# IceCore.net
KiCad netlist of a schematic drawn in EAGLE
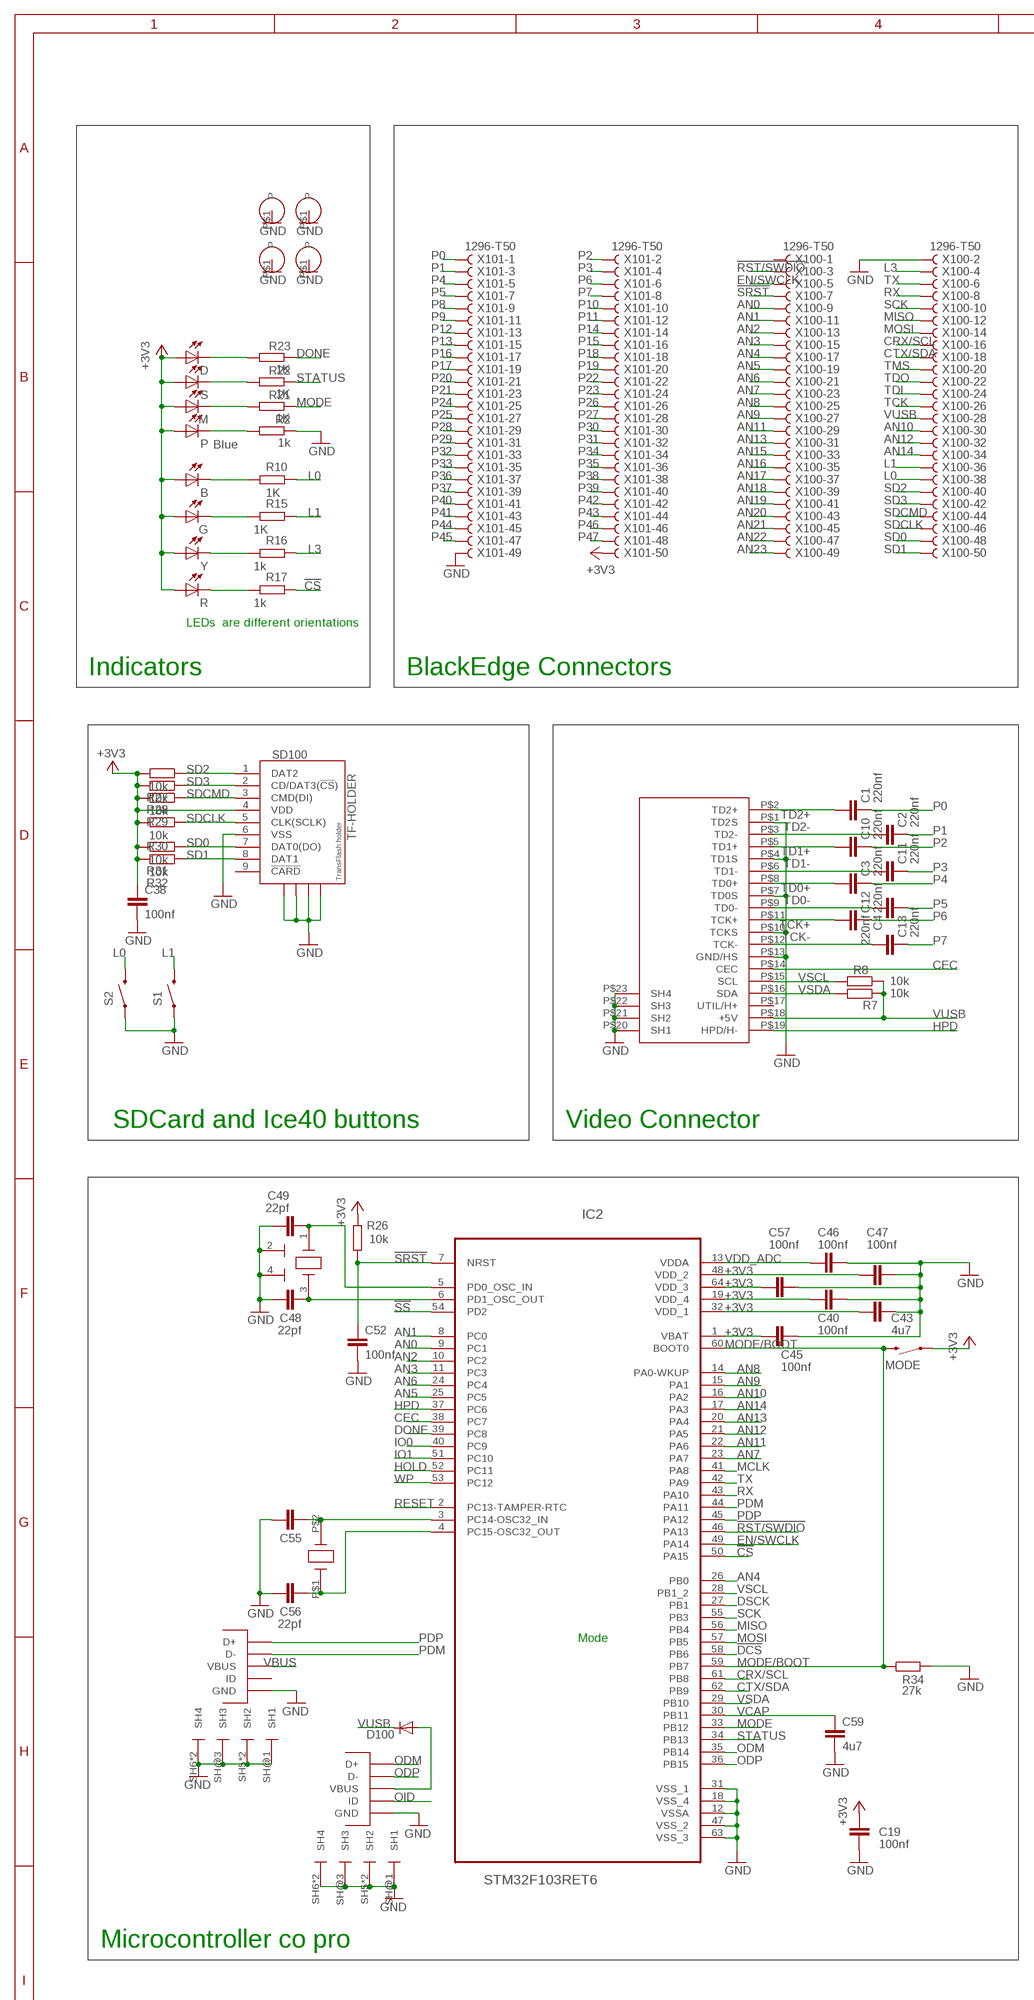
[diagram p0: schematic, sheet 1, part 1 of 2]
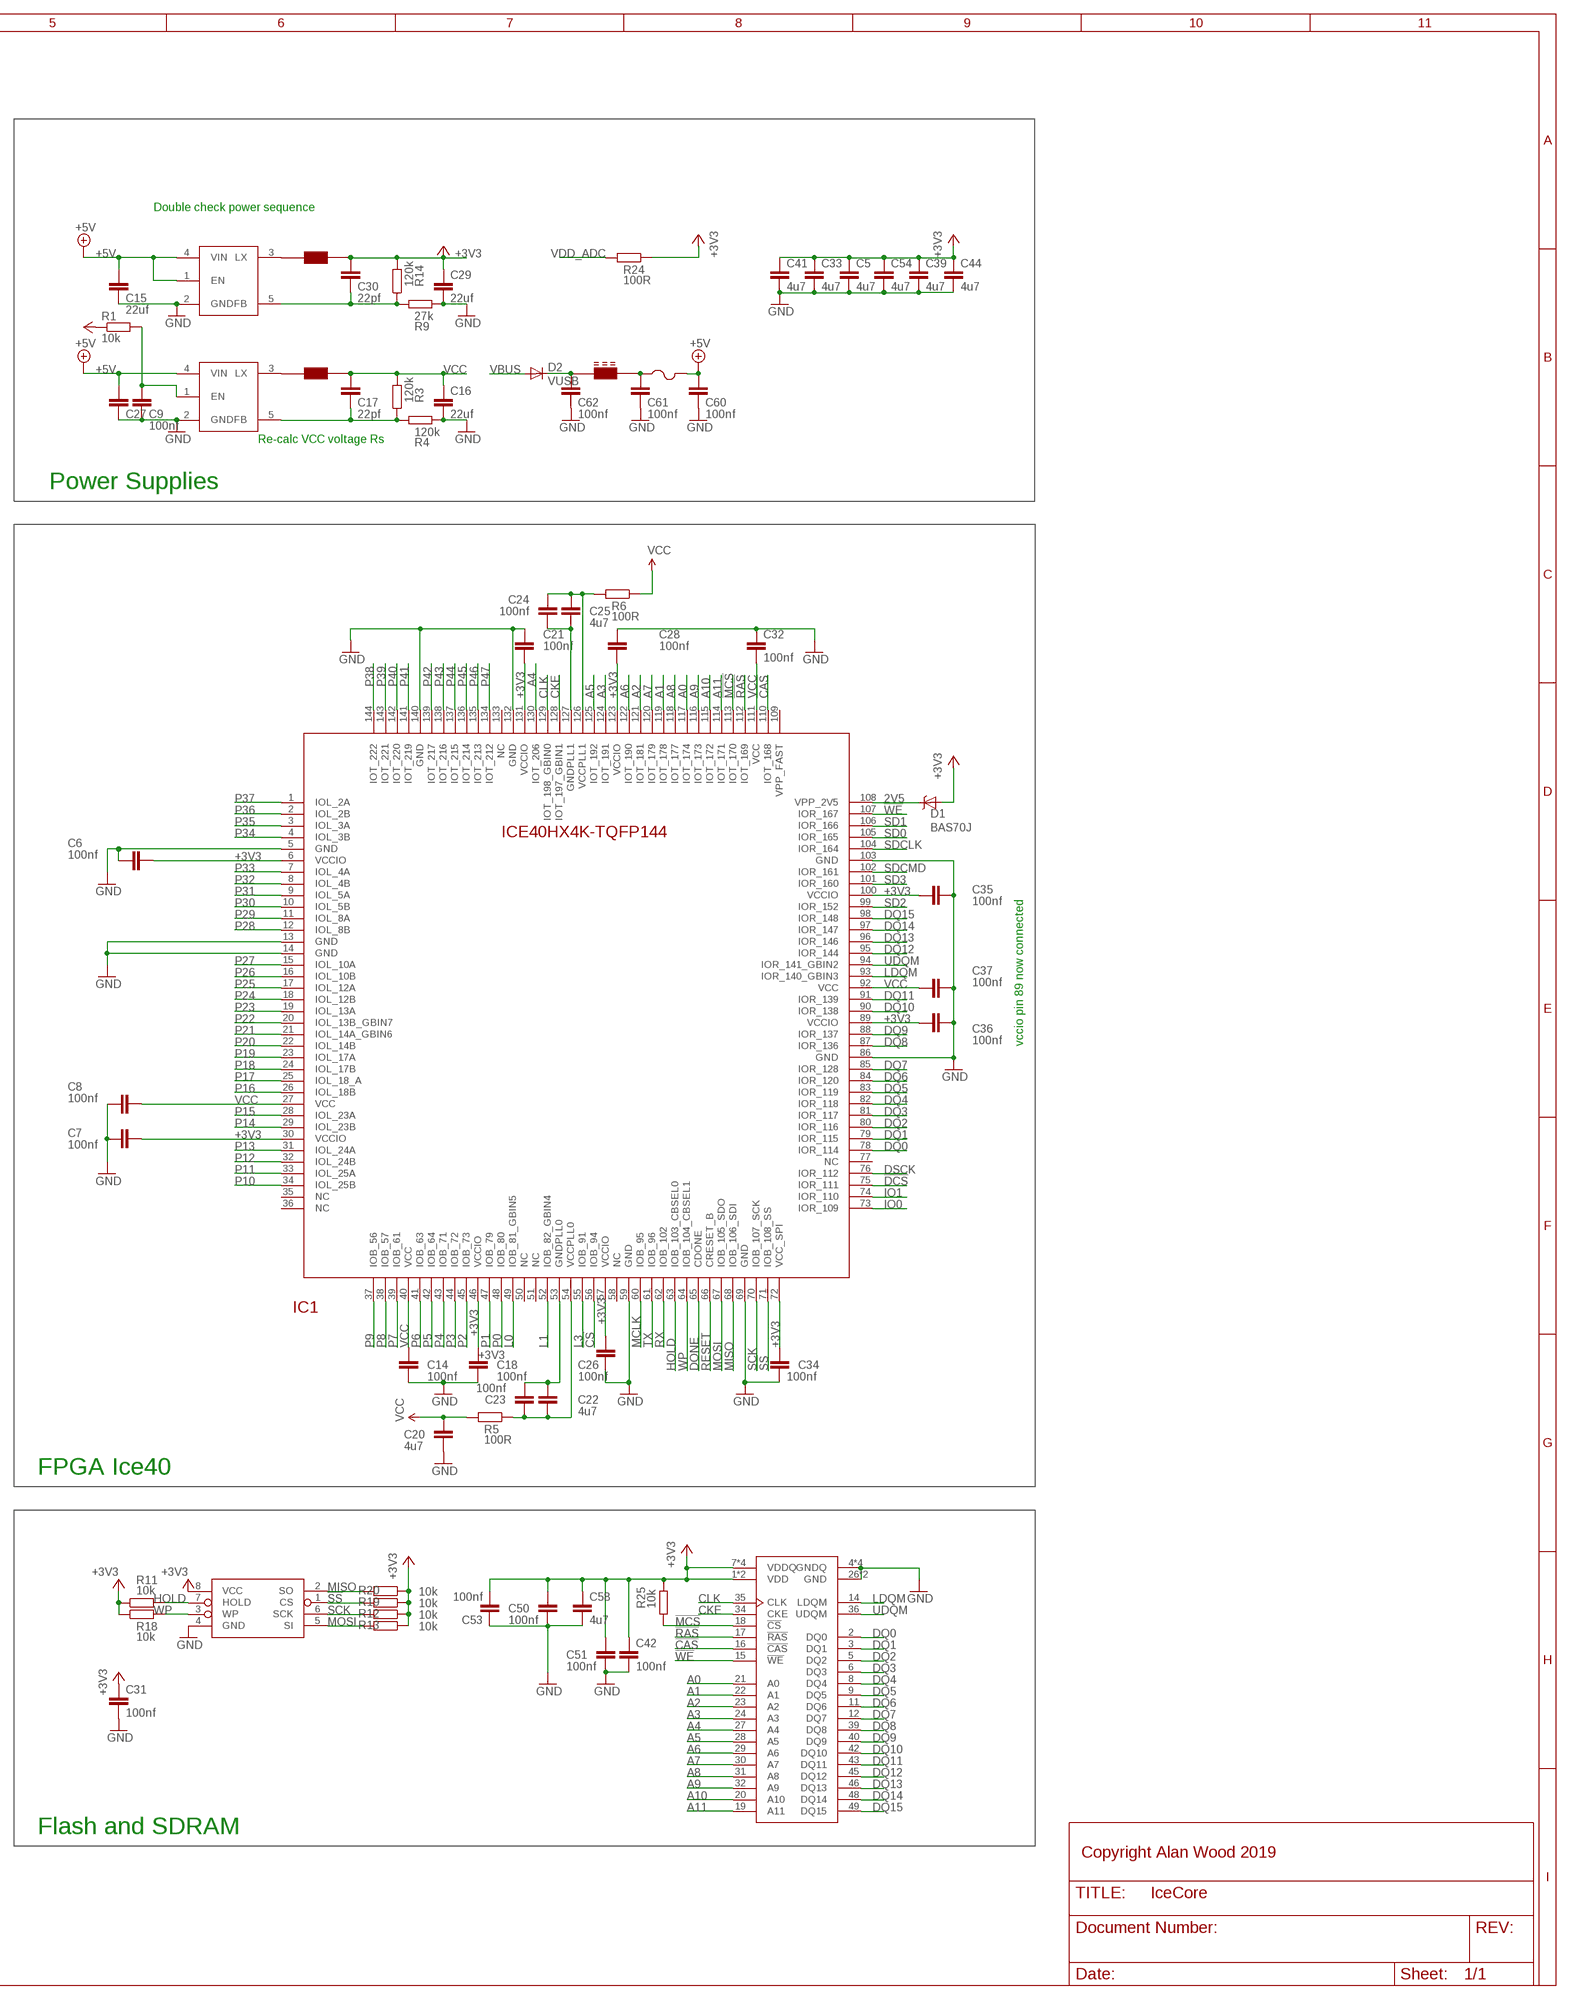
[diagram p1: schematic, sheet 1, part 2 of 2]

(export (version "E")
  (design (tool "Eeschema 10.0.6"))
  (components
    (comp (ref "B")
      (value "LEDCHIPLED_0603")
      (footprint "eagle-import:CHIPLED_0603")
      (libsource (lib "eagle-import") (part "LEDCHIPLED_0603"))
    )
    (comp (ref "C1")
      (value "220nf")
      (footprint "eagle-import:C0402")
      (libsource (lib "eagle-import") (part "C-EUC0402"))
    )
    (comp (ref "C2")
      (value "220nf")
      (footprint "eagle-import:C0402")
      (libsource (lib "eagle-import") (part "C-EUC0402"))
    )
    (comp (ref "C3")
      (value "220nf")
      (footprint "eagle-import:C0402")
      (libsource (lib "eagle-import") (part "C-EUC0402"))
    )
    (comp (ref "C4")
      (value "220nf")
      (footprint "eagle-import:C0402")
      (libsource (lib "eagle-import") (part "C-EUC0402"))
    )
    (comp (ref "C5")
      (value "4u7")
      (footprint "eagle-import:C0402")
      (libsource (lib "eagle-import") (part "C-EUC0402"))
    )
    (comp (ref "C6")
      (value "100nf")
      (footprint "eagle-import:C0402")
      (libsource (lib "eagle-import") (part "C-EUC0402"))
    )
    (comp (ref "C7")
      (value "100nf")
      (footprint "eagle-import:C0402")
      (libsource (lib "eagle-import") (part "C-EUC0402"))
    )
    (comp (ref "C8")
      (value "100nf")
      (footprint "eagle-import:C0402")
      (libsource (lib "eagle-import") (part "C-EUC0402"))
    )
    (comp (ref "C9")
      (value "100nf")
      (footprint "eagle-import:C0402")
      (libsource (lib "eagle-import") (part "C-EUC0402"))
    )
    (comp (ref "C10")
      (value "220nf")
      (footprint "eagle-import:C0402")
      (libsource (lib "eagle-import") (part "C-EUC0402"))
    )
    (comp (ref "C11")
      (value "220nf")
      (footprint "eagle-import:C0402")
      (libsource (lib "eagle-import") (part "C-EUC0402"))
    )
    (comp (ref "C12")
      (value "220nf")
      (footprint "eagle-import:C0402")
      (libsource (lib "eagle-import") (part "C-EUC0402"))
    )
    (comp (ref "C13")
      (value "220nf")
      (footprint "eagle-import:C0402")
      (libsource (lib "eagle-import") (part "C-EUC0402"))
    )
    (comp (ref "C14")
      (value "100nf")
      (footprint "eagle-import:C0402")
      (libsource (lib "eagle-import") (part "C-EUC0402"))
    )
    (comp (ref "C15")
      (value "22uf")
      (footprint "eagle-import:C0603")
      (libsource (lib "eagle-import") (part "C-EUC0603"))
    )
    (comp (ref "C16")
      (value "22uf")
      (footprint "eagle-import:C0603")
      (libsource (lib "eagle-import") (part "C-EUC0603"))
    )
    (comp (ref "C17")
      (value "22pf")
      (footprint "eagle-import:C0402")
      (libsource (lib "eagle-import") (part "C-EUC0402"))
    )
    (comp (ref "C18")
      (value "100nf")
      (footprint "eagle-import:C0402")
      (libsource (lib "eagle-import") (part "C-EUC0402"))
    )
    (comp (ref "C19")
      (value "100nf")
      (footprint "eagle-import:C0402")
      (libsource (lib "eagle-import") (part "C-EUC0402"))
    )
    (comp (ref "C20")
      (value "4u7")
      (footprint "eagle-import:C0402")
      (libsource (lib "eagle-import") (part "C-EUC0402"))
    )
    (comp (ref "C21")
      (value "100nf")
      (footprint "eagle-import:C0402")
      (libsource (lib "eagle-import") (part "C-EUC0402"))
    )
    (comp (ref "C22")
      (value "4u7")
      (footprint "eagle-import:C0402")
      (libsource (lib "eagle-import") (part "C-EUC0402"))
    )
    (comp (ref "C23")
      (value "100nf")
      (footprint "eagle-import:C0402")
      (libsource (lib "eagle-import") (part "C-EUC0402"))
    )
    (comp (ref "C24")
      (value "100nf")
      (footprint "eagle-import:C0402")
      (libsource (lib "eagle-import") (part "C-EUC0402"))
    )
    (comp (ref "C25")
      (value "4u7")
      (footprint "eagle-import:C0402")
      (libsource (lib "eagle-import") (part "C-EUC0402"))
    )
    (comp (ref "C26")
      (value "100nf")
      (footprint "eagle-import:C0402")
      (libsource (lib "eagle-import") (part "C-EUC0402"))
    )
    (comp (ref "C27")
      (value "22uf")
      (footprint "eagle-import:C0603")
      (libsource (lib "eagle-import") (part "C-EUC0603"))
    )
    (comp (ref "C28")
      (value "100nf")
      (footprint "eagle-import:C0402")
      (libsource (lib "eagle-import") (part "C-EUC0402"))
    )
    (comp (ref "C29")
      (value "22uf")
      (footprint "eagle-import:C0603")
      (libsource (lib "eagle-import") (part "C-EUC0603"))
    )
    (comp (ref "C30")
      (value "22pf")
      (footprint "eagle-import:C0402")
      (libsource (lib "eagle-import") (part "C-EUC0402"))
    )
    (comp (ref "C31")
      (value "100nf")
      (footprint "eagle-import:C0402")
      (libsource (lib "eagle-import") (part "C-EUC0402"))
    )
    (comp (ref "C32")
      (value "100nf")
      (footprint "eagle-import:C0402")
      (libsource (lib "eagle-import") (part "C-EUC0402"))
    )
    (comp (ref "C33")
      (value "4u7")
      (footprint "eagle-import:C0402")
      (libsource (lib "eagle-import") (part "C-EUC0402"))
    )
    (comp (ref "C34")
      (value "100nf")
      (footprint "eagle-import:C0402")
      (libsource (lib "eagle-import") (part "C-EUC0402"))
    )
    (comp (ref "C35")
      (value "100nf")
      (footprint "eagle-import:C0402")
      (libsource (lib "eagle-import") (part "C-EUC0402"))
    )
    (comp (ref "C36")
      (value "100nf")
      (footprint "eagle-import:C0402")
      (libsource (lib "eagle-import") (part "C-EUC0402"))
    )
    (comp (ref "C37")
      (value "100nf")
      (footprint "eagle-import:C0402")
      (libsource (lib "eagle-import") (part "C-EUC0402"))
    )
    (comp (ref "C38")
      (value "100nf")
      (footprint "eagle-import:C0402")
      (libsource (lib "eagle-import") (part "C-EUC0402"))
    )
    (comp (ref "C39")
      (value "4u7")
      (footprint "eagle-import:C0402")
      (libsource (lib "eagle-import") (part "C-EUC0402"))
    )
    (comp (ref "C40")
      (value "100nf")
      (footprint "eagle-import:C0402")
      (libsource (lib "eagle-import") (part "C-EUC0402"))
    )
    (comp (ref "C41")
      (value "4u7")
      (footprint "eagle-import:C0402")
      (libsource (lib "eagle-import") (part "C-EUC0402"))
    )
    (comp (ref "C42")
      (value "100nf")
      (footprint "eagle-import:C0402")
      (libsource (lib "eagle-import") (part "C-EUC0402"))
    )
    (comp (ref "C43")
      (value "4u7")
      (footprint "eagle-import:C0402")
      (libsource (lib "eagle-import") (part "C-EUC0402"))
    )
    (comp (ref "C44")
      (value "4u7")
      (footprint "eagle-import:C0402")
      (libsource (lib "eagle-import") (part "C-EUC0402"))
    )
    (comp (ref "C45")
      (value "100nf")
      (footprint "eagle-import:C0402")
      (libsource (lib "eagle-import") (part "C-EUC0402"))
    )
    (comp (ref "C46")
      (value "100nf")
      (footprint "eagle-import:C0402")
      (libsource (lib "eagle-import") (part "C-EUC0402"))
    )
    (comp (ref "C47")
      (value "100nf")
      (footprint "eagle-import:C0402")
      (libsource (lib "eagle-import") (part "C-EUC0402"))
    )
    (comp (ref "C48")
      (value "22pf")
      (footprint "eagle-import:C0402")
      (libsource (lib "eagle-import") (part "C-EUC0402"))
    )
    (comp (ref "C49")
      (value "22pf")
      (footprint "eagle-import:C0402")
      (libsource (lib "eagle-import") (part "C-EUC0402"))
    )
    (comp (ref "C50")
      (value "100nf")
      (footprint "eagle-import:C0402")
      (libsource (lib "eagle-import") (part "C-EUC0402"))
    )
    (comp (ref "C51")
      (value "100nf")
      (footprint "eagle-import:C0402")
      (libsource (lib "eagle-import") (part "C-EUC0402"))
    )
    (comp (ref "C52")
      (value "100nf")
      (footprint "eagle-import:C0402")
      (libsource (lib "eagle-import") (part "C-EUC0402"))
    )
    (comp (ref "C53")
      (value "100nf")
      (footprint "eagle-import:C0402")
      (libsource (lib "eagle-import") (part "C-EUC0402"))
    )
    (comp (ref "C54")
      (value "4u7")
      (footprint "eagle-import:C0402")
      (libsource (lib "eagle-import") (part "C-EUC0402"))
    )
    (comp (ref "C55")
      (value "22pf")
      (footprint "eagle-import:C0402")
      (libsource (lib "eagle-import") (part "C-EUC0402"))
    )
    (comp (ref "C56")
      (value "22pf")
      (footprint "eagle-import:C0402")
      (libsource (lib "eagle-import") (part "C-EUC0402"))
    )
    (comp (ref "C57")
      (value "100nf")
      (footprint "eagle-import:C0402")
      (libsource (lib "eagle-import") (part "C-EUC0402"))
    )
    (comp (ref "C58")
      (value "4u7")
      (footprint "eagle-import:C0402")
      (libsource (lib "eagle-import") (part "C-EUC0402"))
    )
    (comp (ref "C59")
      (value "4u7")
      (footprint "eagle-import:C0402")
      (libsource (lib "eagle-import") (part "C-EUC0402"))
    )
    (comp (ref "C60")
      (value "100nf")
      (footprint "eagle-import:C0402")
      (libsource (lib "eagle-import") (part "C-EUC0402"))
    )
    (comp (ref "C61")
      (value "100nf")
      (footprint "eagle-import:C0402")
      (libsource (lib "eagle-import") (part "C-EUC0402"))
    )
    (comp (ref "C62")
      (value "100nf")
      (footprint "eagle-import:C0402")
      (libsource (lib "eagle-import") (part "C-EUC0402"))
    )
    (comp (ref "COM")
      (value "FCI-MICROUSB-B-PEG")
      (footprint "eagle-import:MICROUSB-B-PEG")
      (libsource (lib "eagle-import") (part "FCI-MICROUSB-B-PEG"))
    )
    (comp (ref "D")
      (value "LEDCHIPLED_0603")
      (footprint "eagle-import:CHIPLED_0603")
      (libsource (lib "eagle-import") (part "LEDCHIPLED_0603"))
    )
    (comp (ref "D1")
      (value "BAS70J")
      (footprint "eagle-import:SOD-323")
      (libsource (lib "eagle-import") (part "BAS70J"))
    )
    (comp (ref "D2")
      (value "DIODE-SOD123")
      (footprint "eagle-import:SOD123")
      (libsource (lib "eagle-import") (part "DIODE-SOD123"))
    )
    (comp (ref "D100")
      (value "DIODE-SOD123")
      (footprint "eagle-import:SOD123")
      (libsource (lib "eagle-import") (part "DIODE-SOD123"))
    )
    (comp (ref "F1")
      (value "PTCFUSE-1206")
      (footprint "eagle-import:R1206")
      (libsource (lib "eagle-import") (part "PTCFUSE-1206"))
    )
    (comp (ref "FB1")
      (value "FERRITE_BEAD")
      (footprint "eagle-import:0603")
      (libsource (lib "eagle-import") (part "FERRITE_BEAD"))
    )
    (comp (ref "G")
      (value "LEDCHIPLED_0603")
      (footprint "eagle-import:CHIPLED_0603")
      (libsource (lib "eagle-import") (part "LEDCHIPLED_0603"))
    )
    (comp (ref "IC1")
      (value "ICE40HX4K_TQFP144")
      (footprint "eagle-import:TQFP144")
      (libsource (lib "eagle-import") (part "ICE40HX4K_TQFP144"))
    )
    (comp (ref "IC2")
      (value "STM32F103RET6")
      (footprint "eagle-import:QFP50P1200X1200X160-64N")
      (libsource (lib "eagle-import") (part "STM32F103RET6"))
    )
    (comp (ref "IC3")
      (value "SDRAM")
      (footprint "eagle-import:TSOP-2-50")
      (libsource (lib "eagle-import") (part "SDRAM"))
    )
    (comp (ref "M")
      (value "LEDCHIPLED_0603")
      (footprint "eagle-import:CHIPLED_0603")
      (libsource (lib "eagle-import") (part "LEDCHIPLED_0603"))
    )
    (comp (ref "MODE")
      (value "SWITCH-MOMENTARY-2SMD-1101NE")
      (footprint "eagle-import:TACTILE-SWITCH-1101NE")
      (libsource (lib "eagle-import") (part "SWITCH-MOMENTARY-2SMD-1101NE"))
    )
    (comp (ref "P")
      (value "Blue")
      (footprint "eagle-import:CHIPLED_0603")
      (libsource (lib "eagle-import") (part "LEDCHIPLED_0603"))
    )
    (comp (ref "R")
      (value "LEDCHIPLED_0603")
      (footprint "eagle-import:CHIPLED_0603")
      (libsource (lib "eagle-import") (part "LEDCHIPLED_0603"))
    )
    (comp (ref "R1")
      (value "10k")
      (footprint "eagle-import:R0402")
      (libsource (lib "eagle-import") (part "resistor_R-EU_R0402"))
    )
    (comp (ref "R2")
      (value "1k")
      (footprint "eagle-import:R0402")
      (libsource (lib "eagle-import") (part "resistor_R-EU_R0402"))
    )
    (comp (ref "R3")
      (value "120k")
      (footprint "eagle-import:R0402")
      (libsource (lib "eagle-import") (part "resistor_R-EU_R0402"))
    )
    (comp (ref "R4")
      (value "120k")
      (footprint "eagle-import:R0402")
      (libsource (lib "eagle-import") (part "resistor_R-EU_R0402"))
    )
    (comp (ref "R5")
      (value "100R")
      (footprint "eagle-import:R0402")
      (libsource (lib "eagle-import") (part "resistor_R-EU_R0402"))
    )
    (comp (ref "R6")
      (value "100R")
      (footprint "eagle-import:R0402")
      (libsource (lib "eagle-import") (part "resistor_R-EU_R0402"))
    )
    (comp (ref "R7")
      (value "10k")
      (footprint "eagle-import:R0402")
      (libsource (lib "eagle-import") (part "resistor_R-EU_R0402"))
    )
    (comp (ref "R8")
      (value "10k")
      (footprint "eagle-import:R0402")
      (libsource (lib "eagle-import") (part "resistor_R-EU_R0402"))
    )
    (comp (ref "R9")
      (value "27k")
      (footprint "eagle-import:R0402")
      (libsource (lib "eagle-import") (part "resistor_R-EU_R0402"))
    )
    (comp (ref "R10")
      (value "1K")
      (footprint "eagle-import:R0402")
      (libsource (lib "eagle-import") (part "resistor_R-EU_R0402"))
    )
    (comp (ref "R11")
      (value "10k")
      (footprint "eagle-import:R0402")
      (libsource (lib "eagle-import") (part "resistor_R-EU_R0402"))
    )
    (comp (ref "R12")
      (value "10k")
      (footprint "eagle-import:R0402")
      (libsource (lib "eagle-import") (part "resistor_R-EU_R0402"))
    )
    (comp (ref "R13")
      (value "10k")
      (footprint "eagle-import:R0402")
      (libsource (lib "eagle-import") (part "resistor_R-EU_R0402"))
    )
    (comp (ref "R14")
      (value "120k")
      (footprint "eagle-import:R0402")
      (libsource (lib "eagle-import") (part "resistor_R-EU_R0402"))
    )
    (comp (ref "R15")
      (value "1K")
      (footprint "eagle-import:R0402")
      (libsource (lib "eagle-import") (part "resistor_R-EU_R0402"))
    )
    (comp (ref "R16")
      (value "1k")
      (footprint "eagle-import:R0402")
      (libsource (lib "eagle-import") (part "resistor_R-EU_R0402"))
    )
    (comp (ref "R17")
      (value "1k")
      (footprint "eagle-import:R0402")
      (libsource (lib "eagle-import") (part "resistor_R-EU_R0402"))
    )
    (comp (ref "R18")
      (value "10k")
      (footprint "eagle-import:R0402")
      (libsource (lib "eagle-import") (part "resistor_R-EU_R0402"))
    )
    (comp (ref "R19")
      (value "10k")
      (footprint "eagle-import:R0402")
      (libsource (lib "eagle-import") (part "resistor_R-EU_R0402"))
    )
    (comp (ref "R20")
      (value "10k")
      (footprint "eagle-import:R0402")
      (libsource (lib "eagle-import") (part "resistor_R-EU_R0402"))
    )
    (comp (ref "R21")
      (value "1K")
      (footprint "eagle-import:R0402")
      (libsource (lib "eagle-import") (part "resistor_R-EU_R0402"))
    )
    (comp (ref "R22")
      (value "1K")
      (footprint "eagle-import:R0402")
      (libsource (lib "eagle-import") (part "resistor_R-EU_R0402"))
    )
    (comp (ref "R23")
      (value "1K")
      (footprint "eagle-import:R0402")
      (libsource (lib "eagle-import") (part "resistor_R-EU_R0402"))
    )
    (comp (ref "R24")
      (value "100R")
      (footprint "eagle-import:R0402")
      (libsource (lib "eagle-import") (part "resistor_R-EU_R0402"))
    )
    (comp (ref "R25")
      (value "10k")
      (footprint "eagle-import:R0402")
      (libsource (lib "eagle-import") (part "resistor_R-EU_R0402"))
    )
    (comp (ref "R26")
      (value "10k")
      (footprint "eagle-import:R0402")
      (libsource (lib "eagle-import") (part "R-EU_R0402"))
    )
    (comp (ref "R27")
      (value "10k")
      (footprint "eagle-import:R0402")
      (libsource (lib "eagle-import") (part "resistor_R-EU_R0402"))
    )
    (comp (ref "R28")
      (value "10k")
      (footprint "eagle-import:R0402")
      (libsource (lib "eagle-import") (part "resistor_R-EU_R0402"))
    )
    (comp (ref "R29")
      (value "10k")
      (footprint "eagle-import:R0402")
      (libsource (lib "eagle-import") (part "resistor_R-EU_R0402"))
    )
    (comp (ref "R30")
      (value "10k")
      (footprint "eagle-import:R0402")
      (libsource (lib "eagle-import") (part "resistor_R-EU_R0402"))
    )
    (comp (ref "R31")
      (value "10k")
      (footprint "eagle-import:R0402")
      (libsource (lib "eagle-import") (part "resistor_R-EU_R0402"))
    )
    (comp (ref "R32")
      (value "10k")
      (footprint "eagle-import:R0402")
      (libsource (lib "eagle-import") (part "resistor_R-EU_R0402"))
    )
    (comp (ref "R34")
      (value "27k")
      (footprint "eagle-import:R0402")
      (libsource (lib "eagle-import") (part "resistor_R-EU_R0402"))
    )
    (comp (ref "S")
      (value "LEDCHIPLED_0603")
      (footprint "eagle-import:CHIPLED_0603")
      (libsource (lib "eagle-import") (part "LEDCHIPLED_0603"))
    )
    (comp (ref "S1")
      (value "SWITCH-MOMENTARY-2SMD-1101NE")
      (footprint "eagle-import:TACTILE-SWITCH-1101NE")
      (libsource (lib "eagle-import") (part "SWITCH-MOMENTARY-2SMD-1101NE"))
    )
    (comp (ref "S2")
      (value "SWITCH-MOMENTARY-2SMD-1101NE")
      (footprint "eagle-import:TACTILE-SWITCH-1101NE")
      (libsource (lib "eagle-import") (part "SWITCH-MOMENTARY-2SMD-1101NE"))
    )
    (comp (ref "SD100")
      (value "TF-HOLDER")
      (footprint "eagle-import:TF-PULL")
      (libsource (lib "eagle-import") (part "TF-HOLDER"))
    )
    (comp (ref "U$1")
      (value "HOLE-2.5MM")
      (footprint "eagle-import:2.5MM-HOLE")
      (libsource (lib "eagle-import") (part "HOLE-2.5MM"))
    )
    (comp (ref "U$2")
      (value "HOLE-2.5MM")
      (footprint "eagle-import:2.5MM-HOLE")
      (libsource (lib "eagle-import") (part "HOLE-2.5MM"))
    )
    (comp (ref "U$3")
      (value "AP3429/A")
      (footprint "eagle-import:TSOP-5_SOT23-5")
      (libsource (lib "eagle-import") (part "AP3429/A"))
    )
    (comp (ref "U$4")
      (value "NRS4018")
      (footprint "eagle-import:NRC4018")
      (libsource (lib "eagle-import") (part "NRS4018"))
    )
    (comp (ref "U$5")
      (value "HD10-001_HDMIMINI-HDMI")
      (footprint "eagle-import:MINI-HDMI")
      (libsource (lib "eagle-import") (part "HD10-001_HDMIMINI-HDMI"))
    )
    (comp (ref "U$6")
      (value "AP3429/A")
      (footprint "eagle-import:TSOP-5_SOT23-5")
      (libsource (lib "eagle-import") (part "AP3429/A"))
    )
    (comp (ref "U$7")
      (value "NRS4018")
      (footprint "eagle-import:NRC4018")
      (libsource (lib "eagle-import") (part "NRS4018"))
    )
    (comp (ref "U$8")
      (value "AT25SDF041A")
      (footprint "eagle-import:SOIC-8-NARROW")
      (libsource (lib "eagle-import") (part "AT25SDF041A"))
    )
    (comp (ref "U$10")
      (value "FCI-MICROUSB-B-PEG")
      (footprint "eagle-import:MICROUSB-B-PEG")
      (libsource (lib "eagle-import") (part "FCI-MICROUSB-B-PEG"))
    )
    (comp (ref "U$11")
      (value "FC-135")
      (footprint "eagle-import:FC135")
      (libsource (lib "eagle-import") (part "FC-135"))
    )
    (comp (ref "U$12")
      (value "HOLE-2.5MM")
      (footprint "eagle-import:2.5MM-HOLE")
      (libsource (lib "eagle-import") (part "HOLE-2.5MM"))
    )
    (comp (ref "U$13")
      (value "HOLE-2.5MM")
      (footprint "eagle-import:2.5MM-HOLE")
      (libsource (lib "eagle-import") (part "HOLE-2.5MM"))
    )
    (comp (ref "X100")
      (value "1296-T50")
      (footprint "eagle-import:1296-50")
      (libsource (lib "eagle-import") (part "1296-T50"))
    )
    (comp (ref "X101")
      (value "1296-T50")
      (footprint "eagle-import:1296-50")
      (libsource (lib "eagle-import") (part "1296-T50"))
    )
    (comp (ref "Y")
      (value "LEDCHIPLED_0603")
      (footprint "eagle-import:CHIPLED_0603")
      (libsource (lib "eagle-import") (part "LEDCHIPLED_0603"))
    )
    (comp (ref "Y1")
      (value "12MZ")
      (footprint "eagle-import:CRYSTAL-3.2X2.5")
      (libsource (lib "eagle-import") (part "7M-25"))
    )
  )
  (nets
    (net (code "1") (name "+3V3") (class "Default")
      (node (ref "B") (pin "A") (pinfunction "A_A") (pintype "passive"))
      (node (ref "C18") (pin "1") (pinfunction "1_1") (pintype "passive"))
      (node (ref "C19") (pin "1") (pinfunction "1_1") (pintype "passive"))
      (node (ref "C21") (pin "1") (pinfunction "1_1") (pintype "passive"))
      (node (ref "C26") (pin "1") (pinfunction "1_1") (pintype "passive"))
      (node (ref "C28") (pin "2") (pinfunction "2_2") (pintype "passive"))
      (node (ref "C29") (pin "1") (pinfunction "1_1") (pintype "passive"))
      (node (ref "C30") (pin "2") (pinfunction "2_2") (pintype "passive"))
      (node (ref "C31") (pin "1") (pinfunction "1_1") (pintype "passive"))
      (node (ref "C33") (pin "1") (pinfunction "1_1") (pintype "passive"))
      (node (ref "C34") (pin "1") (pinfunction "1_1") (pintype "passive"))
      (node (ref "C35") (pin "1") (pinfunction "1_1") (pintype "passive"))
      (node (ref "C36") (pin "1") (pinfunction "1_1") (pintype "passive"))
      (node (ref "C38") (pin "1") (pinfunction "1_1") (pintype "passive"))
      (node (ref "C39") (pin "1") (pinfunction "1_1") (pintype "passive"))
      (node (ref "C40") (pin "2") (pinfunction "2_2") (pintype "passive"))
      (node (ref "C41") (pin "1") (pinfunction "1_1") (pintype "passive"))
      (node (ref "C42") (pin "1") (pinfunction "1_1") (pintype "passive"))
      (node (ref "C43") (pin "2") (pinfunction "2_2") (pintype "passive"))
      (node (ref "C44") (pin "1") (pinfunction "1_1") (pintype "passive"))
      (node (ref "C45") (pin "2") (pinfunction "2_2") (pintype "passive"))
      (node (ref "C47") (pin "2") (pinfunction "2_2") (pintype "passive"))
      (node (ref "C5") (pin "1") (pinfunction "1_1") (pintype "passive"))
      (node (ref "C50") (pin "1") (pinfunction "1_1") (pintype "passive"))
      (node (ref "C51") (pin "1") (pinfunction "1_1") (pintype "passive"))
      (node (ref "C53") (pin "2") (pinfunction "2_2") (pintype "passive"))
      (node (ref "C54") (pin "1") (pinfunction "1_1") (pintype "passive"))
      (node (ref "C57") (pin "2") (pinfunction "2_2") (pintype "passive"))
      (node (ref "C58") (pin "1") (pinfunction "1_1") (pintype "passive"))
      (node (ref "C6") (pin "1") (pinfunction "1_1") (pintype "passive"))
      (node (ref "C7") (pin "2") (pinfunction "2_2") (pintype "passive"))
      (node (ref "D") (pin "A") (pinfunction "A_A") (pintype "passive"))
      (node (ref "D1") (pin "A") (pinfunction "A_A") (pintype "passive"))
      (node (ref "G") (pin "A") (pinfunction "A_A") (pintype "passive"))
      (node (ref "IC1") (pin "100") (pinfunction "VCCIO_100") (pintype "bidirectional"))
      (node (ref "IC1") (pin "123") (pinfunction "VCCIO_123") (pintype "bidirectional"))
      (node (ref "IC1") (pin "131") (pinfunction "VCCIO_131") (pintype "bidirectional"))
      (node (ref "IC1") (pin "30") (pinfunction "VCCIO_30") (pintype "bidirectional"))
      (node (ref "IC1") (pin "46") (pinfunction "VCCIO_46") (pintype "bidirectional"))
      (node (ref "IC1") (pin "57") (pinfunction "VCCIO_57") (pintype "bidirectional"))
      (node (ref "IC1") (pin "6") (pinfunction "VCCIO_6") (pintype "bidirectional"))
      (node (ref "IC1") (pin "72") (pinfunction "VCC_SPI_72") (pintype "bidirectional"))
      (node (ref "IC1") (pin "89") (pinfunction "VCCIO_89") (pintype "bidirectional"))
      (node (ref "IC2") (pin "1") (pinfunction "VBAT_1") (pintype "input"))
      (node (ref "IC2") (pin "19") (pinfunction "VDD_4_19") (pintype "power_in"))
      (node (ref "IC2") (pin "32") (pinfunction "VDD_1_32") (pintype "power_in"))
      (node (ref "IC2") (pin "48") (pinfunction "VDD_2_48") (pintype "power_in"))
      (node (ref "IC2") (pin "64") (pinfunction "VDD_3_64") (pintype "power_in"))
      (node (ref "IC3") (pin "1") (pinfunction "VDD_1") (pintype "power_in"))
      (node (ref "IC3") (pin "13") (pinfunction "VDDQ_13") (pintype "power_in"))
      (node (ref "IC3") (pin "25") (pinfunction "VDD_25") (pintype "power_in"))
      (node (ref "IC3") (pin "38") (pinfunction "VDDQ_38") (pintype "power_in"))
      (node (ref "IC3") (pin "44") (pinfunction "VDDQ_44") (pintype "power_in"))
      (node (ref "IC3") (pin "7") (pinfunction "VDDQ_7") (pintype "power_in"))
      (node (ref "M") (pin "A") (pinfunction "A_A") (pintype "passive"))
      (node (ref "MODE") (pin "1") (pinfunction "1_1") (pintype "passive"))
      (node (ref "P") (pin "A") (pinfunction "A_A") (pintype "passive"))
      (node (ref "R") (pin "A") (pinfunction "A_A") (pintype "passive"))
      (node (ref "R1") (pin "1") (pinfunction "1_1") (pintype "passive"))
      (node (ref "R11") (pin "1") (pinfunction "1_1") (pintype "passive"))
      (node (ref "R12") (pin "1") (pinfunction "1_1") (pintype "passive"))
      (node (ref "R13") (pin "1") (pinfunction "1_1") (pintype "passive"))
      (node (ref "R14") (pin "2") (pinfunction "2_2") (pintype "passive"))
      (node (ref "R18") (pin "1") (pinfunction "1_1") (pintype "passive"))
      (node (ref "R19") (pin "1") (pinfunction "1_1") (pintype "passive"))
      (node (ref "R20") (pin "1") (pinfunction "1_1") (pintype "passive"))
      (node (ref "R24") (pin "1") (pinfunction "1_1") (pintype "passive"))
      (node (ref "R25") (pin "2") (pinfunction "2_2") (pintype "passive"))
      (node (ref "R26") (pin "2") (pinfunction "2_2") (pintype "passive"))
      (node (ref "R27") (pin "2") (pinfunction "2_2") (pintype "passive"))
      (node (ref "R28") (pin "2") (pinfunction "2_2") (pintype "passive"))
      (node (ref "R29") (pin "2") (pinfunction "2_2") (pintype "passive"))
      (node (ref "R30") (pin "2") (pinfunction "2_2") (pintype "passive"))
      (node (ref "R31") (pin "2") (pinfunction "2_2") (pintype "passive"))
      (node (ref "R32") (pin "2") (pinfunction "2_2") (pintype "passive"))
      (node (ref "S") (pin "A") (pinfunction "A_A") (pintype "passive"))
      (node (ref "SD100") (pin "4") (pinfunction "VDD_4") (pintype "power_in"))
      (node (ref "U$7") (pin "P$2") (pinfunction "P$2_P$2") (pintype "passive"))
      (node (ref "U$8") (pin "8") (pinfunction "VCC_8") (pintype "power_in"))
      (node (ref "X101") (pin "50") (pinfunction "B_50") (pintype "passive"))
      (node (ref "Y") (pin "A") (pinfunction "A_A") (pintype "passive"))
    )
    (net (code "2") (name "+5V") (class "Default")
      (node (ref "C15") (pin "2") (pinfunction "2_2") (pintype "passive"))
      (node (ref "C27") (pin "2") (pinfunction "2_2") (pintype "passive"))
      (node (ref "C60") (pin "2") (pinfunction "2_2") (pintype "passive"))
      (node (ref "F1") (pin "2") (pinfunction "2_2") (pintype "passive"))
      (node (ref "U$3") (pin "4") (pinfunction "VIN_4") (pintype "power_in"))
      (node (ref "U$6") (pin "1") (pinfunction "EN_1") (pintype "input"))
      (node (ref "U$6") (pin "4") (pinfunction "VIN_4") (pintype "power_in"))
    )
    (net (code "3") (name "/2V5") (class "Default")
      (node (ref "D1") (pin "C") (pinfunction "C_C") (pintype "passive"))
      (node (ref "IC1") (pin "108") (pinfunction "VPP_2V5_108") (pintype "bidirectional"))
    )
    (net (code "4") (name "/A0") (class "Default")
      (node (ref "IC1") (pin "117") (pinfunction "IOT_174_117") (pintype "bidirectional"))
      (node (ref "IC3") (pin "21") (pinfunction "A0_21") (pintype "input"))
    )
    (net (code "5") (name "/A1") (class "Default")
      (node (ref "IC1") (pin "119") (pinfunction "IOT_178_119") (pintype "bidirectional"))
      (node (ref "IC3") (pin "22") (pinfunction "A1_22") (pintype "input"))
    )
    (net (code "6") (name "/A2") (class "Default")
      (node (ref "IC1") (pin "121") (pinfunction "IOT_181_121") (pintype "bidirectional"))
      (node (ref "IC3") (pin "23") (pinfunction "A2_23") (pintype "input"))
    )
    (net (code "7") (name "/A3") (class "Default")
      (node (ref "IC1") (pin "124") (pinfunction "IOT_191_124") (pintype "bidirectional"))
      (node (ref "IC3") (pin "24") (pinfunction "A3_24") (pintype "input"))
    )
    (net (code "8") (name "/A4") (class "Default")
      (node (ref "IC1") (pin "130") (pinfunction "IOT_206_130") (pintype "bidirectional"))
      (node (ref "IC3") (pin "27") (pinfunction "A4_27") (pintype "input"))
    )
    (net (code "9") (name "/A5") (class "Default")
      (node (ref "IC1") (pin "125") (pinfunction "IOT_192_125") (pintype "bidirectional"))
      (node (ref "IC3") (pin "28") (pinfunction "A5_28") (pintype "input"))
    )
    (net (code "10") (name "/A6") (class "Default")
      (node (ref "IC1") (pin "122") (pinfunction "IOT_190_122") (pintype "bidirectional"))
      (node (ref "IC3") (pin "29") (pinfunction "A6_29") (pintype "input"))
    )
    (net (code "11") (name "/A7") (class "Default")
      (node (ref "IC1") (pin "120") (pinfunction "IOT_179_120") (pintype "bidirectional"))
      (node (ref "IC3") (pin "30") (pinfunction "A7_30") (pintype "input"))
    )
    (net (code "12") (name "/A8") (class "Default")
      (node (ref "IC1") (pin "118") (pinfunction "IOT_177_118") (pintype "bidirectional"))
      (node (ref "IC3") (pin "31") (pinfunction "A8_31") (pintype "input"))
    )
    (net (code "13") (name "/A9") (class "Default")
      (node (ref "IC1") (pin "116") (pinfunction "IOT_173_116") (pintype "bidirectional"))
      (node (ref "IC3") (pin "32") (pinfunction "A9_32") (pintype "input"))
    )
    (net (code "14") (name "/A10") (class "Default")
      (node (ref "IC1") (pin "115") (pinfunction "IOT_172_115") (pintype "bidirectional"))
      (node (ref "IC3") (pin "20") (pinfunction "A10_20") (pintype "input"))
    )
    (net (code "15") (name "/A11") (class "Default")
      (node (ref "IC1") (pin "114") (pinfunction "IOT_171_114") (pintype "bidirectional"))
      (node (ref "IC3") (pin "19") (pinfunction "A11_19") (pintype "input"))
    )
    (net (code "16") (name "/AN0") (class "Default")
      (node (ref "IC2") (pin "9") (pinfunction "PC1_9") (pintype "bidirectional"))
      (node (ref "X100") (pin "9") (pinfunction "B_9") (pintype "passive"))
    )
    (net (code "17") (name "/AN1") (class "Default")
      (node (ref "IC2") (pin "8") (pinfunction "PC0_8") (pintype "bidirectional"))
      (node (ref "X100") (pin "11") (pinfunction "B_11") (pintype "passive"))
    )
    (net (code "18") (name "/AN2") (class "Default")
      (node (ref "IC2") (pin "10") (pinfunction "PC2_10") (pintype "bidirectional"))
      (node (ref "X100") (pin "13") (pinfunction "B_13") (pintype "passive"))
    )
    (net (code "19") (name "/AN3") (class "Default")
      (node (ref "IC2") (pin "11") (pinfunction "PC3_11") (pintype "bidirectional"))
      (node (ref "X100") (pin "15") (pinfunction "B_15") (pintype "passive"))
    )
    (net (code "20") (name "/AN4") (class "Default")
      (node (ref "IC2") (pin "26") (pinfunction "PB0_26") (pintype "bidirectional"))
      (node (ref "X100") (pin "17") (pinfunction "B_17") (pintype "passive"))
    )
    (net (code "21") (name "/AN5") (class "Default")
      (node (ref "IC2") (pin "25") (pinfunction "PC5_25") (pintype "bidirectional"))
      (node (ref "X100") (pin "19") (pinfunction "B_19") (pintype "passive"))
    )
    (net (code "22") (name "/AN6") (class "Default")
      (node (ref "IC2") (pin "24") (pinfunction "PC4_24") (pintype "passive"))
      (node (ref "X100") (pin "21") (pinfunction "B_21") (pintype "passive"))
    )
    (net (code "23") (name "/AN7") (class "Default")
      (node (ref "IC2") (pin "23") (pinfunction "PA7_23") (pintype "power_in"))
      (node (ref "X100") (pin "23") (pinfunction "B_23") (pintype "passive"))
    )
    (net (code "24") (name "/AN8") (class "Default")
      (node (ref "IC2") (pin "14") (pinfunction "PA0-WKUP_14") (pintype "bidirectional"))
      (node (ref "X100") (pin "25") (pinfunction "B_25") (pintype "passive"))
    )
    (net (code "25") (name "/AN9") (class "Default")
      (node (ref "IC2") (pin "15") (pinfunction "PA1_15") (pintype "bidirectional"))
      (node (ref "X100") (pin "27") (pinfunction "B_27") (pintype "passive"))
    )
    (net (code "26") (name "/AN10") (class "Default")
      (node (ref "IC2") (pin "16") (pinfunction "PA2_16") (pintype "bidirectional"))
      (node (ref "X100") (pin "30") (pinfunction "B_30") (pintype "passive"))
    )
    (net (code "27") (name "/AN11") (class "Default")
      (node (ref "IC2") (pin "22") (pinfunction "PA6_22") (pintype "bidirectional"))
      (node (ref "X100") (pin "29") (pinfunction "B_29") (pintype "passive"))
    )
    (net (code "28") (name "/AN12") (class "Default")
      (node (ref "IC2") (pin "21") (pinfunction "PA5_21") (pintype "bidirectional"))
      (node (ref "X100") (pin "32") (pinfunction "B_32") (pintype "passive"))
    )
    (net (code "29") (name "/AN13") (class "Default")
      (node (ref "IC2") (pin "20") (pinfunction "PA4_20") (pintype "bidirectional"))
      (node (ref "X100") (pin "31") (pinfunction "B_31") (pintype "passive"))
    )
    (net (code "30") (name "/AN14") (class "Default")
      (node (ref "IC2") (pin "17") (pinfunction "PA3_17") (pintype "bidirectional"))
      (node (ref "X100") (pin "34") (pinfunction "B_34") (pintype "passive"))
    )
    (net (code "31") (name "/AN15") (class "Default")
      (node (ref "X100") (pin "33") (pinfunction "B_33") (pintype "passive"))
    )
    (net (code "32") (name "/AN16") (class "Default")
      (node (ref "X100") (pin "35") (pinfunction "B_35") (pintype "passive"))
    )
    (net (code "33") (name "/AN17") (class "Default")
      (node (ref "X100") (pin "37") (pinfunction "B_37") (pintype "passive"))
    )
    (net (code "34") (name "/AN18") (class "Default")
      (node (ref "X100") (pin "39") (pinfunction "B_39") (pintype "passive"))
    )
    (net (code "35") (name "/AN19") (class "Default")
      (node (ref "X100") (pin "41") (pinfunction "B_41") (pintype "passive"))
    )
    (net (code "36") (name "/AN20") (class "Default")
      (node (ref "X100") (pin "43") (pinfunction "B_43") (pintype "passive"))
    )
    (net (code "37") (name "/AN21") (class "Default")
      (node (ref "X100") (pin "45") (pinfunction "B_45") (pintype "passive"))
    )
    (net (code "38") (name "/AN22") (class "Default")
      (node (ref "X100") (pin "47") (pinfunction "B_47") (pintype "passive"))
    )
    (net (code "39") (name "/AN23") (class "Default")
      (node (ref "X100") (pin "49") (pinfunction "B_49") (pintype "passive"))
    )
    (net (code "40") (name "/CEC") (class "Default")
      (node (ref "IC2") (pin "38") (pinfunction "PC7_38") (pintype "bidirectional"))
      (node (ref "U$5") (pin "P$14") (pinfunction "CEC_P$14") (pintype "bidirectional"))
    )
    (net (code "41") (name "/CKE") (class "Default")
      (node (ref "IC1") (pin "128") (pinfunction "IOT_197_GBIN1_128") (pintype "bidirectional"))
      (node (ref "IC3") (pin "34") (pinfunction "CKE_34") (pintype "input"))
    )
    (net (code "42") (name "/CLK") (class "Default")
      (node (ref "IC1") (pin "129") (pinfunction "IOT_198_GBIN0_129") (pintype "bidirectional"))
      (node (ref "IC3") (pin "35") (pinfunction "CLK_35") (pintype "input"))
    )
    (net (code "43") (name "/CRX{slash}SCL") (class "Default")
      (node (ref "IC2") (pin "61") (pinfunction "PB8_61") (pintype "bidirectional"))
      (node (ref "X100") (pin "16") (pinfunction "B_16") (pintype "passive"))
    )
    (net (code "44") (name "/CTX{slash}SDA") (class "Default")
      (node (ref "IC2") (pin "62") (pinfunction "PB9_62") (pintype "bidirectional"))
      (node (ref "X100") (pin "18") (pinfunction "B_18") (pintype "passive"))
    )
    (net (code "45") (name "/DONE") (class "Default")
      (node (ref "IC1") (pin "65") (pinfunction "CDONE_65") (pintype "bidirectional"))
      (node (ref "IC2") (pin "39") (pinfunction "PC8_39") (pintype "bidirectional"))
      (node (ref "R23") (pin "1") (pinfunction "1_1") (pintype "passive"))
    )
    (net (code "46") (name "/DQ0") (class "Default")
      (node (ref "IC1") (pin "78") (pinfunction "IOR_114_78") (pintype "bidirectional"))
      (node (ref "IC3") (pin "2") (pinfunction "DQ0_2") (pintype "bidirectional"))
    )
    (net (code "47") (name "/DQ1") (class "Default")
      (node (ref "IC1") (pin "79") (pinfunction "IOR_115_79") (pintype "bidirectional"))
      (node (ref "IC3") (pin "3") (pinfunction "DQ1_3") (pintype "bidirectional"))
    )
    (net (code "48") (name "/DQ2") (class "Default")
      (node (ref "IC1") (pin "80") (pinfunction "IOR_116_80") (pintype "bidirectional"))
      (node (ref "IC3") (pin "5") (pinfunction "DQ2_5") (pintype "bidirectional"))
    )
    (net (code "49") (name "/DQ3") (class "Default")
      (node (ref "IC1") (pin "81") (pinfunction "IOR_117_81") (pintype "bidirectional"))
      (node (ref "IC3") (pin "6") (pinfunction "DQ3_6") (pintype "bidirectional"))
    )
    (net (code "50") (name "/DQ4") (class "Default")
      (node (ref "IC1") (pin "82") (pinfunction "IOR_118_82") (pintype "bidirectional"))
      (node (ref "IC3") (pin "8") (pinfunction "DQ4_8") (pintype "bidirectional"))
    )
    (net (code "51") (name "/DQ5") (class "Default")
      (node (ref "IC1") (pin "83") (pinfunction "IOR_119_83") (pintype "bidirectional"))
      (node (ref "IC3") (pin "9") (pinfunction "DQ5_9") (pintype "bidirectional"))
    )
    (net (code "52") (name "/DQ6") (class "Default")
      (node (ref "IC1") (pin "84") (pinfunction "IOR_120_84") (pintype "bidirectional"))
      (node (ref "IC3") (pin "11") (pinfunction "DQ6_11") (pintype "bidirectional"))
    )
    (net (code "53") (name "/DQ7") (class "Default")
      (node (ref "IC1") (pin "85") (pinfunction "IOR_128_85") (pintype "bidirectional"))
      (node (ref "IC3") (pin "12") (pinfunction "DQ7_12") (pintype "bidirectional"))
    )
    (net (code "54") (name "/DQ8") (class "Default")
      (node (ref "IC1") (pin "87") (pinfunction "IOR_136_87") (pintype "bidirectional"))
      (node (ref "IC3") (pin "39") (pinfunction "DQ8_39") (pintype "bidirectional"))
    )
    (net (code "55") (name "/DQ9") (class "Default")
      (node (ref "IC1") (pin "88") (pinfunction "IOR_137_88") (pintype "bidirectional"))
      (node (ref "IC3") (pin "40") (pinfunction "DQ9_40") (pintype "bidirectional"))
    )
    (net (code "56") (name "/DQ10") (class "Default")
      (node (ref "IC1") (pin "90") (pinfunction "IOR_138_90") (pintype "bidirectional"))
      (node (ref "IC3") (pin "42") (pinfunction "DQ10_42") (pintype "bidirectional"))
    )
    (net (code "57") (name "/DQ11") (class "Default")
      (node (ref "IC1") (pin "91") (pinfunction "IOR_139_91") (pintype "bidirectional"))
      (node (ref "IC3") (pin "43") (pinfunction "DQ11_43") (pintype "bidirectional"))
    )
    (net (code "58") (name "/DQ12") (class "Default")
      (node (ref "IC1") (pin "95") (pinfunction "IOR_144_95") (pintype "bidirectional"))
      (node (ref "IC3") (pin "45") (pinfunction "DQ12_45") (pintype "bidirectional"))
    )
    (net (code "59") (name "/DQ13") (class "Default")
      (node (ref "IC1") (pin "96") (pinfunction "IOR_146_96") (pintype "bidirectional"))
      (node (ref "IC3") (pin "46") (pinfunction "DQ13_46") (pintype "bidirectional"))
    )
    (net (code "60") (name "/DQ14") (class "Default")
      (node (ref "IC1") (pin "97") (pinfunction "IOR_147_97") (pintype "bidirectional"))
      (node (ref "IC3") (pin "48") (pinfunction "DQ14_48") (pintype "bidirectional"))
    )
    (net (code "61") (name "/DQ15") (class "Default")
      (node (ref "IC1") (pin "98") (pinfunction "IOR_148_98") (pintype "bidirectional"))
      (node (ref "IC3") (pin "49") (pinfunction "DQ15_49") (pintype "bidirectional"))
    )
    (net (code "62") (name "/DSCK") (class "Default")
      (node (ref "IC1") (pin "76") (pinfunction "IOR_112_76") (pintype "bidirectional"))
      (node (ref "IC2") (pin "27") (pinfunction "PB1_27") (pintype "bidirectional"))
    )
    (net (code "63") (name "/EN{slash}SWCLK") (class "Default")
      (node (ref "IC2") (pin "49") (pinfunction "PA14_49") (pintype "bidirectional"))
      (node (ref "X100") (pin "5") (pinfunction "B_5") (pintype "passive"))
    )
    (net (code "64") (name "/HOLD") (class "Default")
      (node (ref "IC1") (pin "63") (pinfunction "IOB_103_CBSEL0_63") (pintype "bidirectional"))
      (node (ref "IC2") (pin "52") (pinfunction "PC11_52") (pintype "bidirectional"))
      (node (ref "R11") (pin "2") (pinfunction "2_2") (pintype "passive"))
      (node (ref "U$8") (pin "7") (pinfunction "HOLD_7") (pintype "bidirectional"))
    )
    (net (code "65") (name "/HPD") (class "Default")
      (node (ref "IC2") (pin "37") (pinfunction "PC6_37") (pintype "bidirectional"))
      (node (ref "U$5") (pin "P$19") (pinfunction "HPD/H-_P$19") (pintype "bidirectional"))
    )
    (net (code "66") (name "/IO0") (class "Default")
      (node (ref "IC1") (pin "73") (pinfunction "IOR_109_73") (pintype "bidirectional"))
      (node (ref "IC2") (pin "40") (pinfunction "PC9_40") (pintype "bidirectional"))
    )
    (net (code "67") (name "/IO1") (class "Default")
      (node (ref "IC1") (pin "74") (pinfunction "IOR_110_74") (pintype "bidirectional"))
      (node (ref "IC2") (pin "51") (pinfunction "PC10_51") (pintype "bidirectional"))
    )
    (net (code "68") (name "/L0") (class "Default")
      (node (ref "IC1") (pin "49") (pinfunction "IOB_81_GBIN5_49") (pintype "bidirectional"))
      (node (ref "R10") (pin "2") (pinfunction "2_2") (pintype "passive"))
      (node (ref "S2") (pin "2") (pinfunction "2_2") (pintype "passive"))
      (node (ref "X100") (pin "38") (pinfunction "B_38") (pintype "passive"))
    )
    (net (code "69") (name "/L1") (class "Default")
      (node (ref "IC1") (pin "52") (pinfunction "IOB_82_GBIN4_52") (pintype "bidirectional"))
      (node (ref "R15") (pin "2") (pinfunction "2_2") (pintype "passive"))
      (node (ref "S1") (pin "2") (pinfunction "2_2") (pintype "passive"))
      (node (ref "X100") (pin "36") (pinfunction "B_36") (pintype "passive"))
    )
    (net (code "70") (name "/L3") (class "Default")
      (node (ref "IC1") (pin "55") (pinfunction "IOB_91_55") (pintype "bidirectional"))
      (node (ref "R16") (pin "2") (pinfunction "2_2") (pintype "passive"))
      (node (ref "X100") (pin "4") (pinfunction "B_4") (pintype "passive"))
    )
    (net (code "71") (name "/LDQM") (class "Default")
      (node (ref "IC1") (pin "93") (pinfunction "IOR_140_GBIN3_93") (pintype "bidirectional"))
      (node (ref "IC3") (pin "14") (pinfunction "LDQM_14") (pintype "bidirectional"))
    )
    (net (code "72") (name "/MCLK") (class "Default")
      (node (ref "IC1") (pin "60") (pinfunction "IOB_95_60") (pintype "bidirectional"))
      (node (ref "IC2") (pin "41") (pinfunction "PA8_41") (pintype "bidirectional"))
    )
    (net (code "73") (name "/MISO") (class "Default")
      (node (ref "IC1") (pin "68") (pinfunction "IOB_106_SDI_68") (pintype "bidirectional"))
      (node (ref "IC2") (pin "56") (pinfunction "PB4_56") (pintype "bidirectional"))
      (node (ref "R20") (pin "2") (pinfunction "2_2") (pintype "passive"))
      (node (ref "U$8") (pin "2") (pinfunction "SO_2") (pintype "bidirectional"))
      (node (ref "X100") (pin "12") (pinfunction "B_12") (pintype "passive"))
    )
    (net (code "74") (name "/MODE") (class "Default")
      (node (ref "IC2") (pin "33") (pinfunction "PB12_33") (pintype "bidirectional"))
      (node (ref "R21") (pin "1") (pinfunction "1_1") (pintype "passive"))
    )
    (net (code "75") (name "/MODE{slash}BOOT") (class "Default")
      (node (ref "IC2") (pin "59") (pinfunction "PB7_59") (pintype "power_in"))
      (node (ref "IC2") (pin "60") (pinfunction "BOOT0_60") (pintype "passive"))
      (node (ref "MODE") (pin "2") (pinfunction "2_2") (pintype "passive"))
      (node (ref "R34") (pin "1") (pinfunction "1_1") (pintype "passive"))
    )
    (net (code "76") (name "/MOSI") (class "Default")
      (node (ref "IC1") (pin "67") (pinfunction "IOB_105_SDO_67") (pintype "bidirectional"))
      (node (ref "IC2") (pin "57") (pinfunction "PB5_57") (pintype "bidirectional"))
      (node (ref "R13") (pin "2") (pinfunction "2_2") (pintype "passive"))
      (node (ref "U$8") (pin "5") (pinfunction "SI_5") (pintype "bidirectional"))
      (node (ref "X100") (pin "14") (pinfunction "B_14") (pintype "passive"))
    )
    (net (code "77") (name "/ODM") (class "Default")
      (node (ref "COM") (pin "P$3") (pinfunction "D+_P$3") (pintype "bidirectional"))
      (node (ref "IC2") (pin "35") (pinfunction "PB14_35") (pintype "bidirectional"))
    )
    (net (code "78") (name "/ODP") (class "Default")
      (node (ref "COM") (pin "P$2") (pinfunction "D-_P$2") (pintype "bidirectional"))
      (node (ref "IC2") (pin "36") (pinfunction "PB15_36") (pintype "bidirectional"))
    )
    (net (code "79") (name "/OID") (class "Default")
      (node (ref "COM") (pin "P$4") (pinfunction "ID_P$4") (pintype "bidirectional"))
    )
    (net (code "80") (name "/P0") (class "Default")
      (node (ref "C1") (pin "1") (pinfunction "1_1") (pintype "passive"))
      (node (ref "IC1") (pin "48") (pinfunction "IOB_80_48") (pintype "bidirectional"))
      (node (ref "X101") (pin "1") (pinfunction "B_1") (pintype "passive"))
    )
    (net (code "81") (name "/P1") (class "Default")
      (node (ref "C2") (pin "1") (pinfunction "1_1") (pintype "passive"))
      (node (ref "IC1") (pin "47") (pinfunction "IOB_79_47") (pintype "bidirectional"))
      (node (ref "X101") (pin "3") (pinfunction "B_3") (pintype "passive"))
    )
    (net (code "82") (name "/P2") (class "Default")
      (node (ref "C10") (pin "1") (pinfunction "1_1") (pintype "passive"))
      (node (ref "IC1") (pin "45") (pinfunction "IOB_73_45") (pintype "bidirectional"))
      (node (ref "X101") (pin "2") (pinfunction "B_2") (pintype "passive"))
    )
    (net (code "83") (name "/P3") (class "Default")
      (node (ref "C11") (pin "1") (pinfunction "1_1") (pintype "passive"))
      (node (ref "IC1") (pin "44") (pinfunction "IOB_72_44") (pintype "bidirectional"))
      (node (ref "X101") (pin "4") (pinfunction "B_4") (pintype "passive"))
    )
    (net (code "84") (name "/P4") (class "Default")
      (node (ref "C3") (pin "1") (pinfunction "1_1") (pintype "passive"))
      (node (ref "IC1") (pin "43") (pinfunction "IOB_71_43") (pintype "bidirectional"))
      (node (ref "X101") (pin "5") (pinfunction "B_5") (pintype "passive"))
    )
    (net (code "85") (name "/P5") (class "Default")
      (node (ref "C4") (pin "2") (pinfunction "2_2") (pintype "passive"))
      (node (ref "IC1") (pin "42") (pinfunction "IOB_64_42") (pintype "bidirectional"))
      (node (ref "X101") (pin "7") (pinfunction "B_7") (pintype "passive"))
    )
    (net (code "86") (name "/P6") (class "Default")
      (node (ref "C12") (pin "1") (pinfunction "1_1") (pintype "passive"))
      (node (ref "IC1") (pin "41") (pinfunction "IOB_63_41") (pintype "bidirectional"))
      (node (ref "X101") (pin "6") (pinfunction "B_6") (pintype "passive"))
    )
    (net (code "87") (name "/P7") (class "Default")
      (node (ref "C13") (pin "1") (pinfunction "1_1") (pintype "passive"))
      (node (ref "IC1") (pin "39") (pinfunction "IOB_61_39") (pintype "bidirectional"))
      (node (ref "X101") (pin "8") (pinfunction "B_8") (pintype "passive"))
    )
    (net (code "88") (name "/P8") (class "Default")
      (node (ref "IC1") (pin "38") (pinfunction "IOB_57_38") (pintype "bidirectional"))
      (node (ref "X101") (pin "9") (pinfunction "B_9") (pintype "passive"))
    )
    (net (code "89") (name "/P9") (class "Default")
      (node (ref "IC1") (pin "37") (pinfunction "IOB_56_37") (pintype "bidirectional"))
      (node (ref "X101") (pin "11") (pinfunction "B_11") (pintype "passive"))
    )
    (net (code "90") (name "/P10") (class "Default")
      (node (ref "IC1") (pin "34") (pinfunction "IOL_25B_34") (pintype "bidirectional"))
      (node (ref "X101") (pin "10") (pinfunction "B_10") (pintype "passive"))
    )
    (net (code "91") (name "/P11") (class "Default")
      (node (ref "IC1") (pin "33") (pinfunction "IOL_25A_33") (pintype "bidirectional"))
      (node (ref "X101") (pin "12") (pinfunction "B_12") (pintype "passive"))
    )
    (net (code "92") (name "/P12") (class "Default")
      (node (ref "IC1") (pin "32") (pinfunction "IOL_24B_32") (pintype "bidirectional"))
      (node (ref "X101") (pin "13") (pinfunction "B_13") (pintype "passive"))
    )
    (net (code "93") (name "/P13") (class "Default")
      (node (ref "IC1") (pin "31") (pinfunction "IOL_24A_31") (pintype "bidirectional"))
      (node (ref "X101") (pin "15") (pinfunction "B_15") (pintype "passive"))
    )
    (net (code "94") (name "/P14") (class "Default")
      (node (ref "IC1") (pin "29") (pinfunction "IOL_23B_29") (pintype "bidirectional"))
      (node (ref "X101") (pin "14") (pinfunction "B_14") (pintype "passive"))
    )
    (net (code "95") (name "/P15") (class "Default")
      (node (ref "IC1") (pin "28") (pinfunction "IOL_23A_28") (pintype "bidirectional"))
      (node (ref "X101") (pin "16") (pinfunction "B_16") (pintype "passive"))
    )
    (net (code "96") (name "/P16") (class "Default")
      (node (ref "IC1") (pin "26") (pinfunction "IOL_18B_26") (pintype "bidirectional"))
      (node (ref "X101") (pin "17") (pinfunction "B_17") (pintype "passive"))
    )
    (net (code "97") (name "/P17") (class "Default")
      (node (ref "IC1") (pin "25") (pinfunction "IOL_18_A_25") (pintype "bidirectional"))
      (node (ref "X101") (pin "19") (pinfunction "B_19") (pintype "passive"))
    )
    (net (code "98") (name "/P18") (class "Default")
      (node (ref "IC1") (pin "24") (pinfunction "IOL_17B_24") (pintype "bidirectional"))
      (node (ref "X101") (pin "18") (pinfunction "B_18") (pintype "passive"))
    )
    (net (code "99") (name "/P19") (class "Default")
      (node (ref "IC1") (pin "23") (pinfunction "IOL_17A_23") (pintype "bidirectional"))
      (node (ref "X101") (pin "20") (pinfunction "B_20") (pintype "passive"))
    )
    (net (code "100") (name "/P20") (class "Default")
      (node (ref "IC1") (pin "22") (pinfunction "IOL_14B_22") (pintype "bidirectional"))
      (node (ref "X101") (pin "21") (pinfunction "B_21") (pintype "passive"))
    )
    (net (code "101") (name "/P21") (class "Default")
      (node (ref "IC1") (pin "21") (pinfunction "IOL_14A_GBIN6_21") (pintype "bidirectional"))
      (node (ref "X101") (pin "23") (pinfunction "B_23") (pintype "passive"))
    )
    (net (code "102") (name "/P22") (class "Default")
      (node (ref "IC1") (pin "20") (pinfunction "IOL_13B_GBIN7_20") (pintype "bidirectional"))
      (node (ref "X101") (pin "22") (pinfunction "B_22") (pintype "passive"))
    )
    (net (code "103") (name "/P23") (class "Default")
      (node (ref "IC1") (pin "19") (pinfunction "IOL_13A_19") (pintype "bidirectional"))
      (node (ref "X101") (pin "24") (pinfunction "B_24") (pintype "passive"))
    )
    (net (code "104") (name "/P24") (class "Default")
      (node (ref "IC1") (pin "18") (pinfunction "IOL_12B_18") (pintype "bidirectional"))
      (node (ref "X101") (pin "25") (pinfunction "B_25") (pintype "passive"))
    )
    (net (code "105") (name "/P25") (class "Default")
      (node (ref "IC1") (pin "17") (pinfunction "IOL_12A_17") (pintype "bidirectional"))
      (node (ref "X101") (pin "27") (pinfunction "B_27") (pintype "passive"))
    )
    (net (code "106") (name "/P26") (class "Default")
      (node (ref "IC1") (pin "16") (pinfunction "IOL_10B_16") (pintype "bidirectional"))
      (node (ref "X101") (pin "26") (pinfunction "B_26") (pintype "passive"))
    )
    (net (code "107") (name "/P27") (class "Default")
      (node (ref "IC1") (pin "15") (pinfunction "IOL_10A_15") (pintype "bidirectional"))
      (node (ref "X101") (pin "28") (pinfunction "B_28") (pintype "passive"))
    )
    (net (code "108") (name "/P28") (class "Default")
      (node (ref "IC1") (pin "12") (pinfunction "IOL_8B_12") (pintype "bidirectional"))
      (node (ref "X101") (pin "29") (pinfunction "B_29") (pintype "passive"))
    )
    (net (code "109") (name "/P29") (class "Default")
      (node (ref "IC1") (pin "11") (pinfunction "IOL_8A_11") (pintype "bidirectional"))
      (node (ref "X101") (pin "31") (pinfunction "B_31") (pintype "passive"))
    )
    (net (code "110") (name "/P30") (class "Default")
      (node (ref "IC1") (pin "10") (pinfunction "IOL_5B_10") (pintype "bidirectional"))
      (node (ref "X101") (pin "30") (pinfunction "B_30") (pintype "passive"))
    )
    (net (code "111") (name "/P31") (class "Default")
      (node (ref "IC1") (pin "9") (pinfunction "IOL_5A_9") (pintype "bidirectional"))
      (node (ref "X101") (pin "32") (pinfunction "B_32") (pintype "passive"))
    )
    (net (code "112") (name "/P32") (class "Default")
      (node (ref "IC1") (pin "8") (pinfunction "IOL_4B_8") (pintype "bidirectional"))
      (node (ref "X101") (pin "33") (pinfunction "B_33") (pintype "passive"))
    )
    (net (code "113") (name "/P33") (class "Default")
      (node (ref "IC1") (pin "7") (pinfunction "IOL_4A_7") (pintype "bidirectional"))
      (node (ref "X101") (pin "35") (pinfunction "B_35") (pintype "passive"))
    )
    (net (code "114") (name "/P34") (class "Default")
      (node (ref "IC1") (pin "4") (pinfunction "IOL_3B_4") (pintype "bidirectional"))
      (node (ref "X101") (pin "34") (pinfunction "B_34") (pintype "passive"))
    )
    (net (code "115") (name "/P35") (class "Default")
      (node (ref "IC1") (pin "3") (pinfunction "IOL_3A_3") (pintype "bidirectional"))
      (node (ref "X101") (pin "36") (pinfunction "B_36") (pintype "passive"))
    )
    (net (code "116") (name "/P36") (class "Default")
      (node (ref "IC1") (pin "2") (pinfunction "IOL_2B_2") (pintype "bidirectional"))
      (node (ref "X101") (pin "37") (pinfunction "B_37") (pintype "passive"))
    )
    (net (code "117") (name "/P37") (class "Default")
      (node (ref "IC1") (pin "1") (pinfunction "IOL_2A_1") (pintype "bidirectional"))
      (node (ref "X101") (pin "39") (pinfunction "B_39") (pintype "passive"))
    )
    (net (code "118") (name "/P38") (class "Default")
      (node (ref "IC1") (pin "144") (pinfunction "IOT_222_144") (pintype "bidirectional"))
      (node (ref "X101") (pin "38") (pinfunction "B_38") (pintype "passive"))
    )
    (net (code "119") (name "/P39") (class "Default")
      (node (ref "IC1") (pin "143") (pinfunction "IOT_221_143") (pintype "bidirectional"))
      (node (ref "X101") (pin "40") (pinfunction "B_40") (pintype "passive"))
    )
    (net (code "120") (name "/P40") (class "Default")
      (node (ref "IC1") (pin "142") (pinfunction "IOT_220_142") (pintype "bidirectional"))
      (node (ref "X101") (pin "41") (pinfunction "B_41") (pintype "passive"))
    )
    (net (code "121") (name "/P41") (class "Default")
      (node (ref "IC1") (pin "141") (pinfunction "IOT_219_141") (pintype "bidirectional"))
      (node (ref "X101") (pin "43") (pinfunction "B_43") (pintype "passive"))
    )
    (net (code "122") (name "/P42") (class "Default")
      (node (ref "IC1") (pin "139") (pinfunction "IOT_217_139") (pintype "bidirectional"))
      (node (ref "X101") (pin "42") (pinfunction "B_42") (pintype "passive"))
    )
    (net (code "123") (name "/P43") (class "Default")
      (node (ref "IC1") (pin "138") (pinfunction "IOT_216_138") (pintype "bidirectional"))
      (node (ref "X101") (pin "44") (pinfunction "B_44") (pintype "passive"))
    )
    (net (code "124") (name "/P44") (class "Default")
      (node (ref "IC1") (pin "137") (pinfunction "IOT_215_137") (pintype "bidirectional"))
      (node (ref "X101") (pin "45") (pinfunction "B_45") (pintype "passive"))
    )
    (net (code "125") (name "/P45") (class "Default")
      (node (ref "IC1") (pin "136") (pinfunction "IOT_214_136") (pintype "bidirectional"))
      (node (ref "X101") (pin "47") (pinfunction "B_47") (pintype "passive"))
    )
    (net (code "126") (name "/P46") (class "Default")
      (node (ref "IC1") (pin "135") (pinfunction "IOT_213_135") (pintype "bidirectional"))
      (node (ref "X101") (pin "46") (pinfunction "B_46") (pintype "passive"))
    )
    (net (code "127") (name "/P47") (class "Default")
      (node (ref "IC1") (pin "134") (pinfunction "IOT_212_134") (pintype "bidirectional"))
      (node (ref "X101") (pin "48") (pinfunction "B_48") (pintype "passive"))
    )
    (net (code "128") (name "/PDM") (class "Default")
      (node (ref "IC2") (pin "44") (pinfunction "PA11_44") (pintype "bidirectional"))
      (node (ref "U$10") (pin "P$2") (pinfunction "D-_P$2") (pintype "bidirectional"))
    )
    (net (code "129") (name "/PDP") (class "Default")
      (node (ref "IC2") (pin "45") (pinfunction "PA12_45") (pintype "bidirectional"))
      (node (ref "U$10") (pin "P$3") (pinfunction "D+_P$3") (pintype "bidirectional"))
    )
    (net (code "130") (name "/RESET") (class "Default")
      (node (ref "IC1") (pin "66") (pinfunction "CRESET_B_66") (pintype "bidirectional"))
      (node (ref "IC2") (pin "2") (pinfunction "PC13-TAMPER-RTC_2") (pintype "input"))
    )
    (net (code "131") (name "/RX") (class "Default")
      (node (ref "IC1") (pin "62") (pinfunction "IOB_102_62") (pintype "bidirectional"))
      (node (ref "IC2") (pin "43") (pinfunction "PA10_43") (pintype "bidirectional"))
      (node (ref "X100") (pin "8") (pinfunction "B_8") (pintype "passive"))
    )
    (net (code "132") (name "/SCK") (class "Default")
      (node (ref "IC1") (pin "70") (pinfunction "IOB_107_SCK_70") (pintype "bidirectional"))
      (node (ref "IC2") (pin "55") (pinfunction "PB3_55") (pintype "bidirectional"))
      (node (ref "R12") (pin "2") (pinfunction "2_2") (pintype "passive"))
      (node (ref "U$8") (pin "6") (pinfunction "SCK_6") (pintype "bidirectional"))
      (node (ref "X100") (pin "10") (pinfunction "B_10") (pintype "passive"))
    )
    (net (code "133") (name "/SD0") (class "Default")
      (node (ref "IC1") (pin "105") (pinfunction "IOR_165_105") (pintype "bidirectional"))
      (node (ref "R31") (pin "1") (pinfunction "1_1") (pintype "passive"))
      (node (ref "SD100") (pin "7") (pinfunction "DAT0(DO)_7") (pintype "bidirectional"))
      (node (ref "X100") (pin "48") (pinfunction "B_48") (pintype "passive"))
    )
    (net (code "134") (name "/SD1") (class "Default")
      (node (ref "IC1") (pin "106") (pinfunction "IOR_166_106") (pintype "bidirectional"))
      (node (ref "R32") (pin "1") (pinfunction "1_1") (pintype "passive"))
      (node (ref "SD100") (pin "8") (pinfunction "DAT1_8") (pintype "bidirectional"))
      (node (ref "X100") (pin "50") (pinfunction "B_50") (pintype "passive"))
    )
    (net (code "135") (name "/SD2") (class "Default")
      (node (ref "IC1") (pin "99") (pinfunction "IOR_152_99") (pintype "bidirectional"))
      (node (ref "R27") (pin "1") (pinfunction "1_1") (pintype "passive"))
      (node (ref "SD100") (pin "1") (pinfunction "DAT2_1") (pintype "bidirectional"))
      (node (ref "X100") (pin "40") (pinfunction "B_40") (pintype "passive"))
    )
    (net (code "136") (name "/SD3") (class "Default")
      (node (ref "IC1") (pin "101") (pinfunction "IOR_160_101") (pintype "bidirectional"))
      (node (ref "R28") (pin "1") (pinfunction "1_1") (pintype "passive"))
      (node (ref "SD100") (pin "2") (pinfunction "CD/DAT3(~{CS})_2") (pintype "bidirectional"))
      (node (ref "X100") (pin "42") (pinfunction "B_42") (pintype "passive"))
    )
    (net (code "137") (name "/SDCLK") (class "Default")
      (node (ref "IC1") (pin "104") (pinfunction "IOR_164_104") (pintype "bidirectional"))
      (node (ref "R30") (pin "1") (pinfunction "1_1") (pintype "passive"))
      (node (ref "SD100") (pin "5") (pinfunction "CLK(SCLK)_5") (pintype "input"))
      (node (ref "X100") (pin "46") (pinfunction "B_46") (pintype "passive"))
    )
    (net (code "138") (name "/SDCMD") (class "Default")
      (node (ref "IC1") (pin "102") (pinfunction "IOR_161_102") (pintype "bidirectional"))
      (node (ref "R29") (pin "1") (pinfunction "1_1") (pintype "passive"))
      (node (ref "SD100") (pin "3") (pinfunction "CMD(DI)_3") (pintype "bidirectional"))
      (node (ref "X100") (pin "44") (pinfunction "B_44") (pintype "passive"))
    )
    (net (code "139") (name "/STATUS") (class "Default")
      (node (ref "IC2") (pin "34") (pinfunction "PB13_34") (pintype "bidirectional"))
      (node (ref "R22") (pin "1") (pinfunction "1_1") (pintype "passive"))
    )
    (net (code "140") (name "/TCK") (class "Default")
      (node (ref "X100") (pin "26") (pinfunction "B_26") (pintype "passive"))
    )
    (net (code "141") (name "/TCK+") (class "Default")
      (node (ref "C12") (pin "2") (pinfunction "2_2") (pintype "passive"))
      (node (ref "U$5") (pin "P$11") (pinfunction "TCK+_P$11") (pintype "bidirectional"))
    )
    (net (code "142") (name "/TCK-") (class "Default")
      (node (ref "C13") (pin "2") (pinfunction "2_2") (pintype "passive"))
      (node (ref "U$5") (pin "P$12") (pinfunction "TCK-_P$12") (pintype "bidirectional"))
    )
    (net (code "143") (name "/TD0+") (class "Default")
      (node (ref "C3") (pin "2") (pinfunction "2_2") (pintype "passive"))
      (node (ref "U$5") (pin "P$8") (pinfunction "TD0+_P$8") (pintype "bidirectional"))
    )
    (net (code "144") (name "/TD0-") (class "Default")
      (node (ref "C4") (pin "1") (pinfunction "1_1") (pintype "passive"))
      (node (ref "U$5") (pin "P$9") (pinfunction "TD0-_P$9") (pintype "bidirectional"))
    )
    (net (code "145") (name "/TD1+") (class "Default")
      (node (ref "C10") (pin "2") (pinfunction "2_2") (pintype "passive"))
      (node (ref "U$5") (pin "P$5") (pinfunction "TD1+_P$5") (pintype "bidirectional"))
    )
    (net (code "146") (name "/TD1-") (class "Default")
      (node (ref "C11") (pin "2") (pinfunction "2_2") (pintype "passive"))
      (node (ref "U$5") (pin "P$6") (pinfunction "TD1-_P$6") (pintype "bidirectional"))
    )
    (net (code "147") (name "/TD2+") (class "Default")
      (node (ref "C1") (pin "2") (pinfunction "2_2") (pintype "passive"))
      (node (ref "U$5") (pin "P$2") (pinfunction "TD2+_P$2") (pintype "bidirectional"))
    )
    (net (code "148") (name "/TD2-") (class "Default")
      (node (ref "C2") (pin "2") (pinfunction "2_2") (pintype "passive"))
      (node (ref "U$5") (pin "P$3") (pinfunction "TD2-_P$3") (pintype "bidirectional"))
    )
    (net (code "149") (name "/TDI") (class "Default")
      (node (ref "X100") (pin "24") (pinfunction "B_24") (pintype "passive"))
    )
    (net (code "150") (name "/TDO") (class "Default")
      (node (ref "X100") (pin "22") (pinfunction "B_22") (pintype "passive"))
    )
    (net (code "151") (name "/TMS") (class "Default")
      (node (ref "X100") (pin "20") (pinfunction "B_20") (pintype "passive"))
    )
    (net (code "152") (name "/TX") (class "Default")
      (node (ref "IC1") (pin "61") (pinfunction "IOB_96_61") (pintype "bidirectional"))
      (node (ref "IC2") (pin "42") (pinfunction "PA9_42") (pintype "bidirectional"))
      (node (ref "X100") (pin "6") (pinfunction "B_6") (pintype "passive"))
    )
    (net (code "153") (name "/UDQM") (class "Default")
      (node (ref "IC1") (pin "94") (pinfunction "IOR_141_GBIN2_94") (pintype "bidirectional"))
      (node (ref "IC3") (pin "36") (pinfunction "UDQM_36") (pintype "bidirectional"))
    )
    (net (code "154") (name "/VBUS") (class "Default")
      (node (ref "D2") (pin "A") (pinfunction "A_A") (pintype "passive"))
      (node (ref "U$10") (pin "P$1") (pinfunction "VBUS_P$1") (pintype "bidirectional"))
    )
    (net (code "155") (name "/VCAP") (class "Default")
      (node (ref "C59") (pin "1") (pinfunction "1_1") (pintype "passive"))
      (node (ref "IC2") (pin "30") (pinfunction "PB11_30") (pintype "bidirectional"))
    )
    (net (code "156") (name "/VDD_ADC") (class "Default")
      (node (ref "C46") (pin "2") (pinfunction "2_2") (pintype "passive"))
      (node (ref "IC2") (pin "13") (pinfunction "VDDA_13") (pintype "power_in"))
      (node (ref "R24") (pin "2") (pinfunction "2_2") (pintype "passive"))
    )
    (net (code "157") (name "/VSCL") (class "Default")
      (node (ref "IC2") (pin "28") (pinfunction "PB1_2_28") (pintype "bidirectional"))
      (node (ref "R8") (pin "2") (pinfunction "2_2") (pintype "passive"))
      (node (ref "U$5") (pin "P$15") (pinfunction "SCL_P$15") (pintype "bidirectional"))
    )
    (net (code "158") (name "/VSDA") (class "Default")
      (node (ref "IC2") (pin "29") (pinfunction "PB10_29") (pintype "bidirectional"))
      (node (ref "R7") (pin "2") (pinfunction "2_2") (pintype "passive"))
      (node (ref "U$5") (pin "P$16") (pinfunction "SDA_P$16") (pintype "bidirectional"))
    )
    (net (code "159") (name "/VUSB") (class "Default")
      (node (ref "C62") (pin "2") (pinfunction "2_2") (pintype "passive"))
      (node (ref "D100") (pin "C") (pinfunction "C_C") (pintype "passive"))
      (node (ref "D2") (pin "C") (pinfunction "C_C") (pintype "passive"))
      (node (ref "FB1") (pin "1") (pinfunction "P$1_1") (pintype "passive"))
      (node (ref "R7") (pin "1") (pinfunction "1_1") (pintype "passive"))
      (node (ref "R8") (pin "1") (pinfunction "1_1") (pintype "passive"))
      (node (ref "U$5") (pin "P$18") (pinfunction "+5V_P$18") (pintype "power_in"))
      (node (ref "X100") (pin "28") (pinfunction "B_28") (pintype "passive"))
    )
    (net (code "160") (name "/WP") (class "Default")
      (node (ref "IC1") (pin "64") (pinfunction "IOB_104_CBSEL1_64") (pintype "bidirectional"))
      (node (ref "IC2") (pin "53") (pinfunction "PC12_53") (pintype "bidirectional"))
      (node (ref "R18") (pin "2") (pinfunction "2_2") (pintype "passive"))
      (node (ref "U$8") (pin "3") (pinfunction "WP_3") (pintype "bidirectional"))
    )
    (net (code "161") (name "/~{CAS}") (class "Default")
      (node (ref "IC1") (pin "110") (pinfunction "IOT_168_110") (pintype "bidirectional"))
      (node (ref "IC3") (pin "16") (pinfunction "~{CAS}_16") (pintype "input"))
    )
    (net (code "162") (name "/~{CS}") (class "Default")
      (node (ref "IC1") (pin "56") (pinfunction "IOB_94_56") (pintype "bidirectional"))
      (node (ref "IC2") (pin "50") (pinfunction "PA15_50") (pintype "bidirectional"))
      (node (ref "R17") (pin "2") (pinfunction "2_2") (pintype "passive"))
    )
    (net (code "163") (name "/~{DCS}") (class "Default")
      (node (ref "IC1") (pin "75") (pinfunction "IOR_111_75") (pintype "bidirectional"))
      (node (ref "IC2") (pin "58") (pinfunction "PB6_58") (pintype "bidirectional"))
    )
    (net (code "164") (name "/~{MCS}") (class "Default")
      (node (ref "IC1") (pin "113") (pinfunction "IOT_170_113") (pintype "bidirectional"))
      (node (ref "IC3") (pin "18") (pinfunction "~{CS}_18") (pintype "input"))
      (node (ref "R25") (pin "1") (pinfunction "1_1") (pintype "passive"))
    )
    (net (code "165") (name "/~{RAS}") (class "Default")
      (node (ref "IC1") (pin "112") (pinfunction "IOT_169_112") (pintype "bidirectional"))
      (node (ref "IC3") (pin "17") (pinfunction "~{RAS}_17") (pintype "input"))
    )
    (net (code "166") (name "/~{RST{slash}SWDIO}") (class "Default")
      (node (ref "IC2") (pin "46") (pinfunction "PA13_46") (pintype "bidirectional"))
      (node (ref "X100") (pin "3") (pinfunction "B_3") (pintype "passive"))
    )
    (net (code "167") (name "/~{SRST}") (class "Default")
      (node (ref "C52") (pin "1") (pinfunction "1_1") (pintype "passive"))
      (node (ref "IC2") (pin "7") (pinfunction "NRST_7") (pintype "output"))
      (node (ref "R26") (pin "1") (pinfunction "1_1") (pintype "passive"))
      (node (ref "X100") (pin "7") (pinfunction "B_7") (pintype "passive"))
    )
    (net (code "168") (name "/~{SS}") (class "Default")
      (node (ref "IC1") (pin "71") (pinfunction "IOB_108_SS_71") (pintype "bidirectional"))
      (node (ref "IC2") (pin "54") (pinfunction "PD2_54") (pintype "bidirectional"))
      (node (ref "R19") (pin "2") (pinfunction "2_2") (pintype "passive"))
      (node (ref "U$8") (pin "1") (pinfunction "CS_1") (pintype "input"))
    )
    (net (code "169") (name "/~{WE}") (class "Default")
      (node (ref "IC1") (pin "107") (pinfunction "IOR_167_107") (pintype "bidirectional"))
      (node (ref "IC3") (pin "15") (pinfunction "~{WE}_15") (pintype "input"))
    )
    (net (code "170") (name "GND") (class "Default")
      (node (ref "C14") (pin "2") (pinfunction "2_2") (pintype "passive"))
      (node (ref "C15") (pin "1") (pinfunction "1_1") (pintype "passive"))
      (node (ref "C16") (pin "2") (pinfunction "2_2") (pintype "passive"))
      (node (ref "C18") (pin "2") (pinfunction "2_2") (pintype "passive"))
      (node (ref "C19") (pin "2") (pinfunction "2_2") (pintype "passive"))
      (node (ref "C20") (pin "2") (pinfunction "2_2") (pintype "passive"))
      (node (ref "C21") (pin "2") (pinfunction "2_2") (pintype "passive"))
      (node (ref "C26") (pin "2") (pinfunction "2_2") (pintype "passive"))
      (node (ref "C27") (pin "1") (pinfunction "1_1") (pintype "passive"))
      (node (ref "C28") (pin "1") (pinfunction "1_1") (pintype "passive"))
      (node (ref "C29") (pin "2") (pinfunction "2_2") (pintype "passive"))
      (node (ref "C31") (pin "2") (pinfunction "2_2") (pintype "passive"))
      (node (ref "C32") (pin "1") (pinfunction "1_1") (pintype "passive"))
      (node (ref "C33") (pin "2") (pinfunction "2_2") (pintype "passive"))
      (node (ref "C34") (pin "2") (pinfunction "2_2") (pintype "passive"))
      (node (ref "C35") (pin "2") (pinfunction "2_2") (pintype "passive"))
      (node (ref "C36") (pin "2") (pinfunction "2_2") (pintype "passive"))
      (node (ref "C37") (pin "2") (pinfunction "2_2") (pintype "passive"))
      (node (ref "C38") (pin "2") (pinfunction "2_2") (pintype "passive"))
      (node (ref "C39") (pin "2") (pinfunction "2_2") (pintype "passive"))
      (node (ref "C40") (pin "1") (pinfunction "1_1") (pintype "passive"))
      (node (ref "C41") (pin "2") (pinfunction "2_2") (pintype "passive"))
      (node (ref "C42") (pin "2") (pinfunction "2_2") (pintype "passive"))
      (node (ref "C43") (pin "1") (pinfunction "1_1") (pintype "passive"))
      (node (ref "C44") (pin "2") (pinfunction "2_2") (pintype "passive"))
      (node (ref "C45") (pin "1") (pinfunction "1_1") (pintype "passive"))
      (node (ref "C46") (pin "1") (pinfunction "1_1") (pintype "passive"))
      (node (ref "C47") (pin "1") (pinfunction "1_1") (pintype "passive"))
      (node (ref "C48") (pin "1") (pinfunction "1_1") (pintype "passive"))
      (node (ref "C49") (pin "1") (pinfunction "1_1") (pintype "passive"))
      (node (ref "C5") (pin "2") (pinfunction "2_2") (pintype "passive"))
      (node (ref "C50") (pin "2") (pinfunction "2_2") (pintype "passive"))
      (node (ref "C51") (pin "2") (pinfunction "2_2") (pintype "passive"))
      (node (ref "C52") (pin "2") (pinfunction "2_2") (pintype "passive"))
      (node (ref "C53") (pin "1") (pinfunction "1_1") (pintype "passive"))
      (node (ref "C54") (pin "2") (pinfunction "2_2") (pintype "passive"))
      (node (ref "C55") (pin "1") (pinfunction "1_1") (pintype "passive"))
      (node (ref "C56") (pin "1") (pinfunction "1_1") (pintype "passive"))
      (node (ref "C57") (pin "1") (pinfunction "1_1") (pintype "passive"))
      (node (ref "C58") (pin "2") (pinfunction "2_2") (pintype "passive"))
      (node (ref "C59") (pin "2") (pinfunction "2_2") (pintype "passive"))
      (node (ref "C6") (pin "2") (pinfunction "2_2") (pintype "passive"))
      (node (ref "C60") (pin "1") (pinfunction "1_1") (pintype "passive"))
      (node (ref "C61") (pin "1") (pinfunction "1_1") (pintype "passive"))
      (node (ref "C62") (pin "1") (pinfunction "1_1") (pintype "passive"))
      (node (ref "C7") (pin "1") (pinfunction "1_1") (pintype "passive"))
      (node (ref "C8") (pin "2") (pinfunction "2_2") (pintype "passive"))
      (node (ref "C9") (pin "1") (pinfunction "1_1") (pintype "passive"))
      (node (ref "COM") (pin "P$5") (pinfunction "GND_P$5") (pintype "bidirectional"))
      (node (ref "COM") (pin "SH5") (pinfunction "SH2_SH5") (pintype "bidirectional"))
      (node (ref "COM") (pin "SH6") (pinfunction "SH4_SH6") (pintype "bidirectional"))
      (node (ref "COM") (pin "SH@1") (pinfunction "SH1_SH@1") (pintype "bidirectional"))
      (node (ref "COM") (pin "SH@2") (pinfunction "SH2_SH@2") (pintype "bidirectional"))
      (node (ref "COM") (pin "SH@3") (pinfunction "SH3_SH@3") (pintype "bidirectional"))
      (node (ref "COM") (pin "SH@4") (pinfunction "SH4_SH@4") (pintype "bidirectional"))
      (node (ref "IC1") (pin "103") (pinfunction "GND_103") (pintype "bidirectional"))
      (node (ref "IC1") (pin "13") (pinfunction "GND_13") (pintype "bidirectional"))
      (node (ref "IC1") (pin "132") (pinfunction "GND_132") (pintype "bidirectional"))
      (node (ref "IC1") (pin "14") (pinfunction "GND_14") (pintype "bidirectional"))
      (node (ref "IC1") (pin "140") (pinfunction "GND_140") (pintype "bidirectional"))
      (node (ref "IC1") (pin "5") (pinfunction "GND_5") (pintype "bidirectional"))
      (node (ref "IC1") (pin "59") (pinfunction "GND_59") (pintype "bidirectional"))
      (node (ref "IC1") (pin "69") (pinfunction "GND_69") (pintype "bidirectional"))
      (node (ref "IC1") (pin "86") (pinfunction "GND_86") (pintype "bidirectional"))
      (node (ref "IC2") (pin "12") (pinfunction "VSSA_12") (pintype "passive"))
      (node (ref "IC2") (pin "18") (pinfunction "VSS_4_18") (pintype "passive"))
      (node (ref "IC2") (pin "31") (pinfunction "VSS_1_31") (pintype "passive"))
      (node (ref "IC2") (pin "47") (pinfunction "VSS_2_47") (pintype "passive"))
      (node (ref "IC2") (pin "63") (pinfunction "VSS_3_63") (pintype "passive"))
      (node (ref "IC3") (pin "10") (pinfunction "GNDQ_10") (pintype "bidirectional"))
      (node (ref "IC3") (pin "26") (pinfunction "GND_26") (pintype "bidirectional"))
      (node (ref "IC3") (pin "4") (pinfunction "GNDQ_4") (pintype "bidirectional"))
      (node (ref "IC3") (pin "41") (pinfunction "GNDQ_41") (pintype "bidirectional"))
      (node (ref "IC3") (pin "47") (pinfunction "GNDQ_47") (pintype "bidirectional"))
      (node (ref "IC3") (pin "50") (pinfunction "GND_50") (pintype "bidirectional"))
      (node (ref "R2") (pin "1") (pinfunction "1_1") (pintype "passive"))
      (node (ref "R34") (pin "2") (pinfunction "2_2") (pintype "passive"))
      (node (ref "R4") (pin "2") (pinfunction "2_2") (pintype "passive"))
      (node (ref "R9") (pin "2") (pinfunction "2_2") (pintype "passive"))
      (node (ref "S1") (pin "1") (pinfunction "1_1") (pintype "passive"))
      (node (ref "S2") (pin "1") (pinfunction "1_1") (pintype "passive"))
      (node (ref "SD100") (pin "6") (pinfunction "VSS_6") (pintype "power_in"))
      (node (ref "SD100") (pin "S1") (pinfunction "S1_S1") (pintype "passive"))
      (node (ref "SD100") (pin "S2") (pinfunction "S2_S2") (pintype "passive"))
      (node (ref "SD100") (pin "S3") (pinfunction "S3_S3") (pintype "passive"))
      (node (ref "SD100") (pin "S4") (pinfunction "S4_S4") (pintype "passive"))
      (node (ref "U$1") (pin "P$1") (pinfunction "P_P$1") (pintype "bidirectional"))
      (node (ref "U$10") (pin "P$5") (pinfunction "GND_P$5") (pintype "bidirectional"))
      (node (ref "U$10") (pin "SH5") (pinfunction "SH2_SH5") (pintype "bidirectional"))
      (node (ref "U$10") (pin "SH6") (pinfunction "SH4_SH6") (pintype "bidirectional"))
      (node (ref "U$10") (pin "SH@1") (pinfunction "SH1_SH@1") (pintype "bidirectional"))
      (node (ref "U$10") (pin "SH@2") (pinfunction "SH2_SH@2") (pintype "bidirectional"))
      (node (ref "U$10") (pin "SH@3") (pinfunction "SH3_SH@3") (pintype "bidirectional"))
      (node (ref "U$10") (pin "SH@4") (pinfunction "SH4_SH@4") (pintype "bidirectional"))
      (node (ref "U$12") (pin "P$1") (pinfunction "P_P$1") (pintype "bidirectional"))
      (node (ref "U$13") (pin "P$1") (pinfunction "P_P$1") (pintype "bidirectional"))
      (node (ref "U$2") (pin "P$1") (pinfunction "P_P$1") (pintype "bidirectional"))
      (node (ref "U$3") (pin "2") (pinfunction "GND_2") (pintype "power_in"))
      (node (ref "U$5") (pin "P$1") (pinfunction "TD2S_P$1") (pintype "passive"))
      (node (ref "U$5") (pin "P$10") (pinfunction "TCKS_P$10") (pintype "passive"))
      (node (ref "U$5") (pin "P$13") (pinfunction "GND/HS_P$13") (pintype "power_in"))
      (node (ref "U$5") (pin "P$20") (pinfunction "SH1_P$20") (pintype "passive"))
      (node (ref "U$5") (pin "P$21") (pinfunction "SH2_P$21") (pintype "passive"))
      (node (ref "U$5") (pin "P$22") (pinfunction "SH3_P$22") (pintype "passive"))
      (node (ref "U$5") (pin "P$23") (pinfunction "SH4_P$23") (pintype "passive"))
      (node (ref "U$5") (pin "P$4") (pinfunction "TD1S_P$4") (pintype "passive"))
      (node (ref "U$5") (pin "P$7") (pinfunction "TD0S_P$7") (pintype "passive"))
      (node (ref "U$6") (pin "2") (pinfunction "GND_2") (pintype "power_in"))
      (node (ref "U$8") (pin "4") (pinfunction "GND_4") (pintype "power_in"))
      (node (ref "X100") (pin "2") (pinfunction "B_2") (pintype "passive"))
      (node (ref "X101") (pin "49") (pinfunction "B_49") (pintype "passive"))
      (node (ref "Y1") (pin "2") (pinfunction "GND_2") (pintype "power_in"))
      (node (ref "Y1") (pin "4") (pinfunction "GND_4") (pintype "passive"))
    )
    (net (code "171") (name "Net-(B-PadC)") (class "Default")
      (node (ref "B") (pin "C") (pinfunction "C_C") (pintype "passive"))
      (node (ref "R10") (pin "1") (pinfunction "1_1") (pintype "passive"))
    )
    (net (code "172") (name "Net-(COM-VBUS)") (class "Default")
      (node (ref "COM") (pin "P$1") (pinfunction "VBUS_P$1") (pintype "bidirectional"))
      (node (ref "D100") (pin "A") (pinfunction "A_A") (pintype "passive"))
    )
    (net (code "173") (name "Net-(D-PadC)") (class "Default")
      (node (ref "D") (pin "C") (pinfunction "C_C") (pintype "passive"))
      (node (ref "R23") (pin "2") (pinfunction "2_2") (pintype "passive"))
    )
    (net (code "174") (name "Net-(FB1-P$2)") (class "Default")
      (node (ref "C61") (pin "2") (pinfunction "2_2") (pintype "passive"))
      (node (ref "F1") (pin "1") (pinfunction "1_1") (pintype "passive"))
      (node (ref "FB1") (pin "2") (pinfunction "P$2_2") (pintype "passive"))
    )
    (net (code "175") (name "Net-(G-PadC)") (class "Default")
      (node (ref "G") (pin "C") (pinfunction "C_C") (pintype "passive"))
      (node (ref "R15") (pin "1") (pinfunction "1_1") (pintype "passive"))
    )
    (net (code "176") (name "Net-(IC1-GNDPLL0)") (class "Default")
      (node (ref "C22") (pin "1") (pinfunction "1_1") (pintype "passive"))
      (node (ref "C23") (pin "2") (pinfunction "2_2") (pintype "passive"))
      (node (ref "IC1") (pin "53") (pinfunction "GNDPLL0_53") (pintype "bidirectional"))
    )
    (net (code "177") (name "Net-(IC1-GNDPLL1)") (class "Default")
      (node (ref "C24") (pin "1") (pinfunction "1_1") (pintype "passive"))
      (node (ref "C25") (pin "1") (pinfunction "1_1") (pintype "passive"))
      (node (ref "IC1") (pin "127") (pinfunction "GNDPLL1_127") (pintype "bidirectional"))
    )
    (net (code "178") (name "Net-(IC1-VCCPLL0)") (class "Default")
      (node (ref "C22") (pin "2") (pinfunction "2_2") (pintype "passive"))
      (node (ref "C23") (pin "1") (pinfunction "1_1") (pintype "passive"))
      (node (ref "IC1") (pin "54") (pinfunction "VCCPLL0_54") (pintype "bidirectional"))
      (node (ref "R5") (pin "1") (pinfunction "1_1") (pintype "passive"))
    )
    (net (code "179") (name "Net-(IC1-VCCPLL1)") (class "Default")
      (node (ref "C24") (pin "2") (pinfunction "2_2") (pintype "passive"))
      (node (ref "C25") (pin "2") (pinfunction "2_2") (pintype "passive"))
      (node (ref "IC1") (pin "126") (pinfunction "VCCPLL1_126") (pintype "bidirectional"))
      (node (ref "R6") (pin "2") (pinfunction "2_2") (pintype "passive"))
    )
    (net (code "180") (name "Net-(IC2-PC14-OSC32_IN)") (class "Default")
      (node (ref "C55") (pin "2") (pinfunction "2_2") (pintype "passive"))
      (node (ref "IC2") (pin "3") (pinfunction "PC14-OSC32_IN_3") (pintype "input"))
      (node (ref "U$11") (pin "P$2") (pinfunction "X2_P$2") (pintype "passive"))
    )
    (net (code "181") (name "Net-(IC2-PC15-OSC32_OUT)") (class "Default")
      (node (ref "C56") (pin "2") (pinfunction "2_2") (pintype "passive"))
      (node (ref "IC2") (pin "4") (pinfunction "PC15-OSC32_OUT_4") (pintype "output"))
      (node (ref "U$11") (pin "P$1") (pinfunction "X1_P$1") (pintype "passive"))
    )
    (net (code "182") (name "Net-(IC2-PD0_OSC_IN)") (class "Default")
      (node (ref "C49") (pin "2") (pinfunction "2_2") (pintype "passive"))
      (node (ref "IC2") (pin "5") (pinfunction "PD0_OSC_IN_5") (pintype "input"))
      (node (ref "Y1") (pin "1") (pinfunction "X1_1") (pintype "passive"))
    )
    (net (code "183") (name "Net-(IC2-PD1_OSC_OUT)") (class "Default")
      (node (ref "C48") (pin "2") (pinfunction "2_2") (pintype "passive"))
      (node (ref "IC2") (pin "6") (pinfunction "PD1_OSC_OUT_6") (pintype "output"))
      (node (ref "Y1") (pin "3") (pinfunction "X2_3") (pintype "passive"))
    )
    (net (code "184") (name "Net-(M-PadC)") (class "Default")
      (node (ref "M") (pin "C") (pinfunction "C_C") (pintype "passive"))
      (node (ref "R21") (pin "2") (pinfunction "2_2") (pintype "passive"))
    )
    (net (code "185") (name "Net-(P-PadC)") (class "Default")
      (node (ref "P") (pin "C") (pinfunction "C_C") (pintype "passive"))
      (node (ref "R2") (pin "2") (pinfunction "2_2") (pintype "passive"))
    )
    (net (code "186") (name "Net-(R-PadC)") (class "Default")
      (node (ref "R") (pin "C") (pinfunction "C_C") (pintype "passive"))
      (node (ref "R17") (pin "1") (pinfunction "1_1") (pintype "passive"))
    )
    (net (code "187") (name "Net-(R16-Pad1)") (class "Default")
      (node (ref "R16") (pin "1") (pinfunction "1_1") (pintype "passive"))
      (node (ref "Y") (pin "C") (pinfunction "C_C") (pintype "passive"))
    )
    (net (code "188") (name "Net-(R22-Pad2)") (class "Default")
      (node (ref "R22") (pin "2") (pinfunction "2_2") (pintype "passive"))
      (node (ref "S") (pin "C") (pinfunction "C_C") (pintype "passive"))
    )
    (net (code "189") (name "Net-(U$3-EN)") (class "Default")
      (node (ref "C9") (pin "2") (pinfunction "2_2") (pintype "passive"))
      (node (ref "R1") (pin "2") (pinfunction "2_2") (pintype "passive"))
      (node (ref "U$3") (pin "1") (pinfunction "EN_1") (pintype "input"))
    )
    (net (code "190") (name "Net-(U$3-FB)") (class "Default")
      (node (ref "C17") (pin "1") (pinfunction "1_1") (pintype "passive"))
      (node (ref "R3") (pin "1") (pinfunction "1_1") (pintype "passive"))
      (node (ref "R4") (pin "1") (pinfunction "1_1") (pintype "passive"))
      (node (ref "U$3") (pin "5") (pinfunction "FB_5") (pintype "input"))
    )
    (net (code "191") (name "Net-(U$3-LX)") (class "Default")
      (node (ref "U$3") (pin "3") (pinfunction "LX_3") (pintype "power_in"))
      (node (ref "U$4") (pin "P$1") (pinfunction "P$1_P$1") (pintype "passive"))
    )
    (net (code "192") (name "Net-(U$6-FB)") (class "Default")
      (node (ref "C30") (pin "1") (pinfunction "1_1") (pintype "passive"))
      (node (ref "R14") (pin "1") (pinfunction "1_1") (pintype "passive"))
      (node (ref "R9") (pin "1") (pinfunction "1_1") (pintype "passive"))
      (node (ref "U$6") (pin "5") (pinfunction "FB_5") (pintype "input"))
    )
    (net (code "193") (name "Net-(U$6-LX)") (class "Default")
      (node (ref "U$6") (pin "3") (pinfunction "LX_3") (pintype "power_in"))
      (node (ref "U$7") (pin "P$1") (pinfunction "P$1_P$1") (pintype "passive"))
    )
    (net (code "194") (name "VCC") (class "Default")
      (node (ref "C14") (pin "1") (pinfunction "1_1") (pintype "passive"))
      (node (ref "C16") (pin "1") (pinfunction "1_1") (pintype "passive"))
      (node (ref "C17") (pin "2") (pinfunction "2_2") (pintype "passive"))
      (node (ref "C20") (pin "1") (pinfunction "1_1") (pintype "passive"))
      (node (ref "C32") (pin "2") (pinfunction "2_2") (pintype "passive"))
      (node (ref "C37") (pin "1") (pinfunction "1_1") (pintype "passive"))
      (node (ref "C8") (pin "1") (pinfunction "1_1") (pintype "passive"))
      (node (ref "IC1") (pin "111") (pinfunction "VCC_111") (pintype "bidirectional"))
      (node (ref "IC1") (pin "27") (pinfunction "VCC_27") (pintype "bidirectional"))
      (node (ref "IC1") (pin "40") (pinfunction "VCC_40") (pintype "bidirectional"))
      (node (ref "IC1") (pin "92") (pinfunction "VCC_92") (pintype "bidirectional"))
      (node (ref "R3") (pin "2") (pinfunction "2_2") (pintype "passive"))
      (node (ref "R5") (pin "2") (pinfunction "2_2") (pintype "passive"))
      (node (ref "R6") (pin "1") (pinfunction "1_1") (pintype "passive"))
      (node (ref "U$4") (pin "P$2") (pinfunction "P$2_P$2") (pintype "passive"))
    )
    (net (code "195") (name "unconnected-(IC1-NC-Pad35)") (class "Default")
      (node (ref "IC1") (pin "35") (pinfunction "NC_35") (pintype "bidirectional"))
    )
    (net (code "196") (name "unconnected-(IC1-NC-Pad36)") (class "Default")
      (node (ref "IC1") (pin "36") (pinfunction "NC_36") (pintype "bidirectional"))
    )
    (net (code "197") (name "unconnected-(IC1-NC-Pad50)") (class "Default")
      (node (ref "IC1") (pin "50") (pinfunction "NC_50") (pintype "bidirectional"))
    )
    (net (code "198") (name "unconnected-(IC1-NC-Pad51)") (class "Default")
      (node (ref "IC1") (pin "51") (pinfunction "NC_51") (pintype "bidirectional"))
    )
    (net (code "199") (name "unconnected-(IC1-NC-Pad58)") (class "Default")
      (node (ref "IC1") (pin "58") (pinfunction "NC_58") (pintype "bidirectional"))
    )
    (net (code "200") (name "unconnected-(IC1-NC-Pad77)") (class "Default")
      (node (ref "IC1") (pin "77") (pinfunction "NC_77") (pintype "bidirectional"))
    )
    (net (code "201") (name "unconnected-(IC1-NC-Pad133)") (class "Default")
      (node (ref "IC1") (pin "133") (pinfunction "NC_133") (pintype "bidirectional"))
    )
    (net (code "202") (name "unconnected-(IC1-VPP_FAST-Pad109)") (class "Default")
      (node (ref "IC1") (pin "109") (pinfunction "VPP_FAST_109") (pintype "bidirectional"))
    )
    (net (code "203") (name "unconnected-(IC3-NC-Pad33)") (class "Default")
      (node (ref "IC3") (pin "33") (pinfunction "NC_33") (pintype "no_connect"))
    )
    (net (code "204") (name "unconnected-(IC3-NC-Pad37)") (class "Default")
      (node (ref "IC3") (pin "37") (pinfunction "NC_37") (pintype "no_connect"))
    )
    (net (code "205") (name "unconnected-(SD100-~{CARD}-Pad9)") (class "Default")
      (node (ref "SD100") (pin "9") (pinfunction "~{CARD}_9") (pintype "passive"))
    )
    (net (code "206") (name "unconnected-(U$5-UTIL{slash}H+-PadP$17)") (class "Default")
      (node (ref "U$5") (pin "P$17") (pinfunction "UTIL/H+_P$17") (pintype "bidirectional"))
    )
    (net (code "207") (name "unconnected-(U$10-ID-PadP$4)") (class "Default")
      (node (ref "U$10") (pin "P$4") (pinfunction "ID_P$4") (pintype "bidirectional"))
    )
    (net (code "208") (name "unconnected-(X100A-B-Pad1)") (class "Default")
      (node (ref "X100") (pin "1") (pinfunction "B_1") (pintype "passive"))
    )
  )
)
